# soundpuddle_megawing_mk1.net
KiCad netlist of a schematic drawn in EAGLE
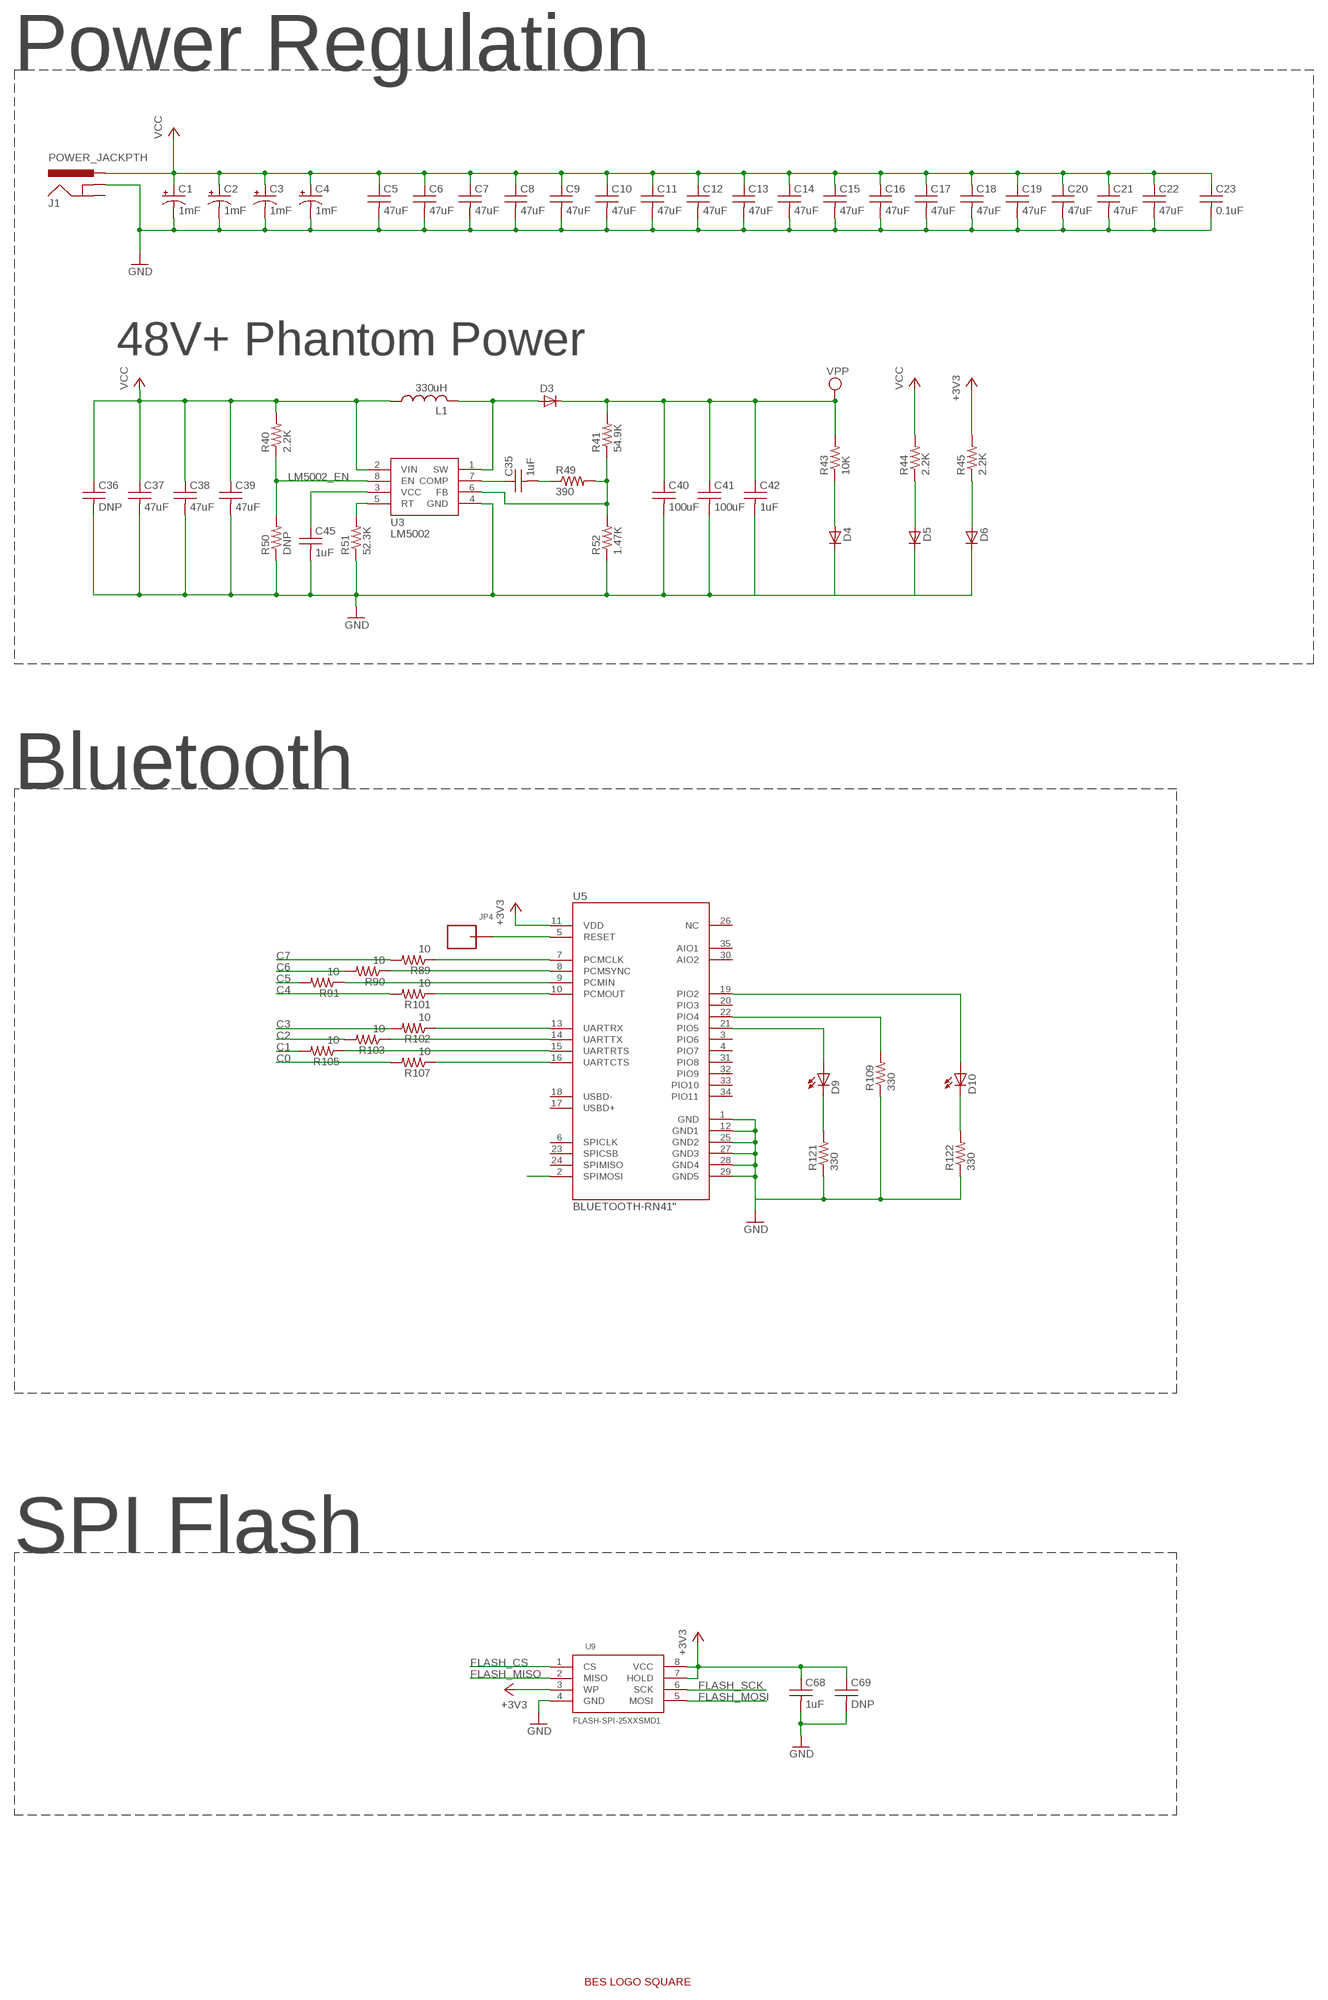
[diagram p0: schematic, sheet 1, part 1 of 3]
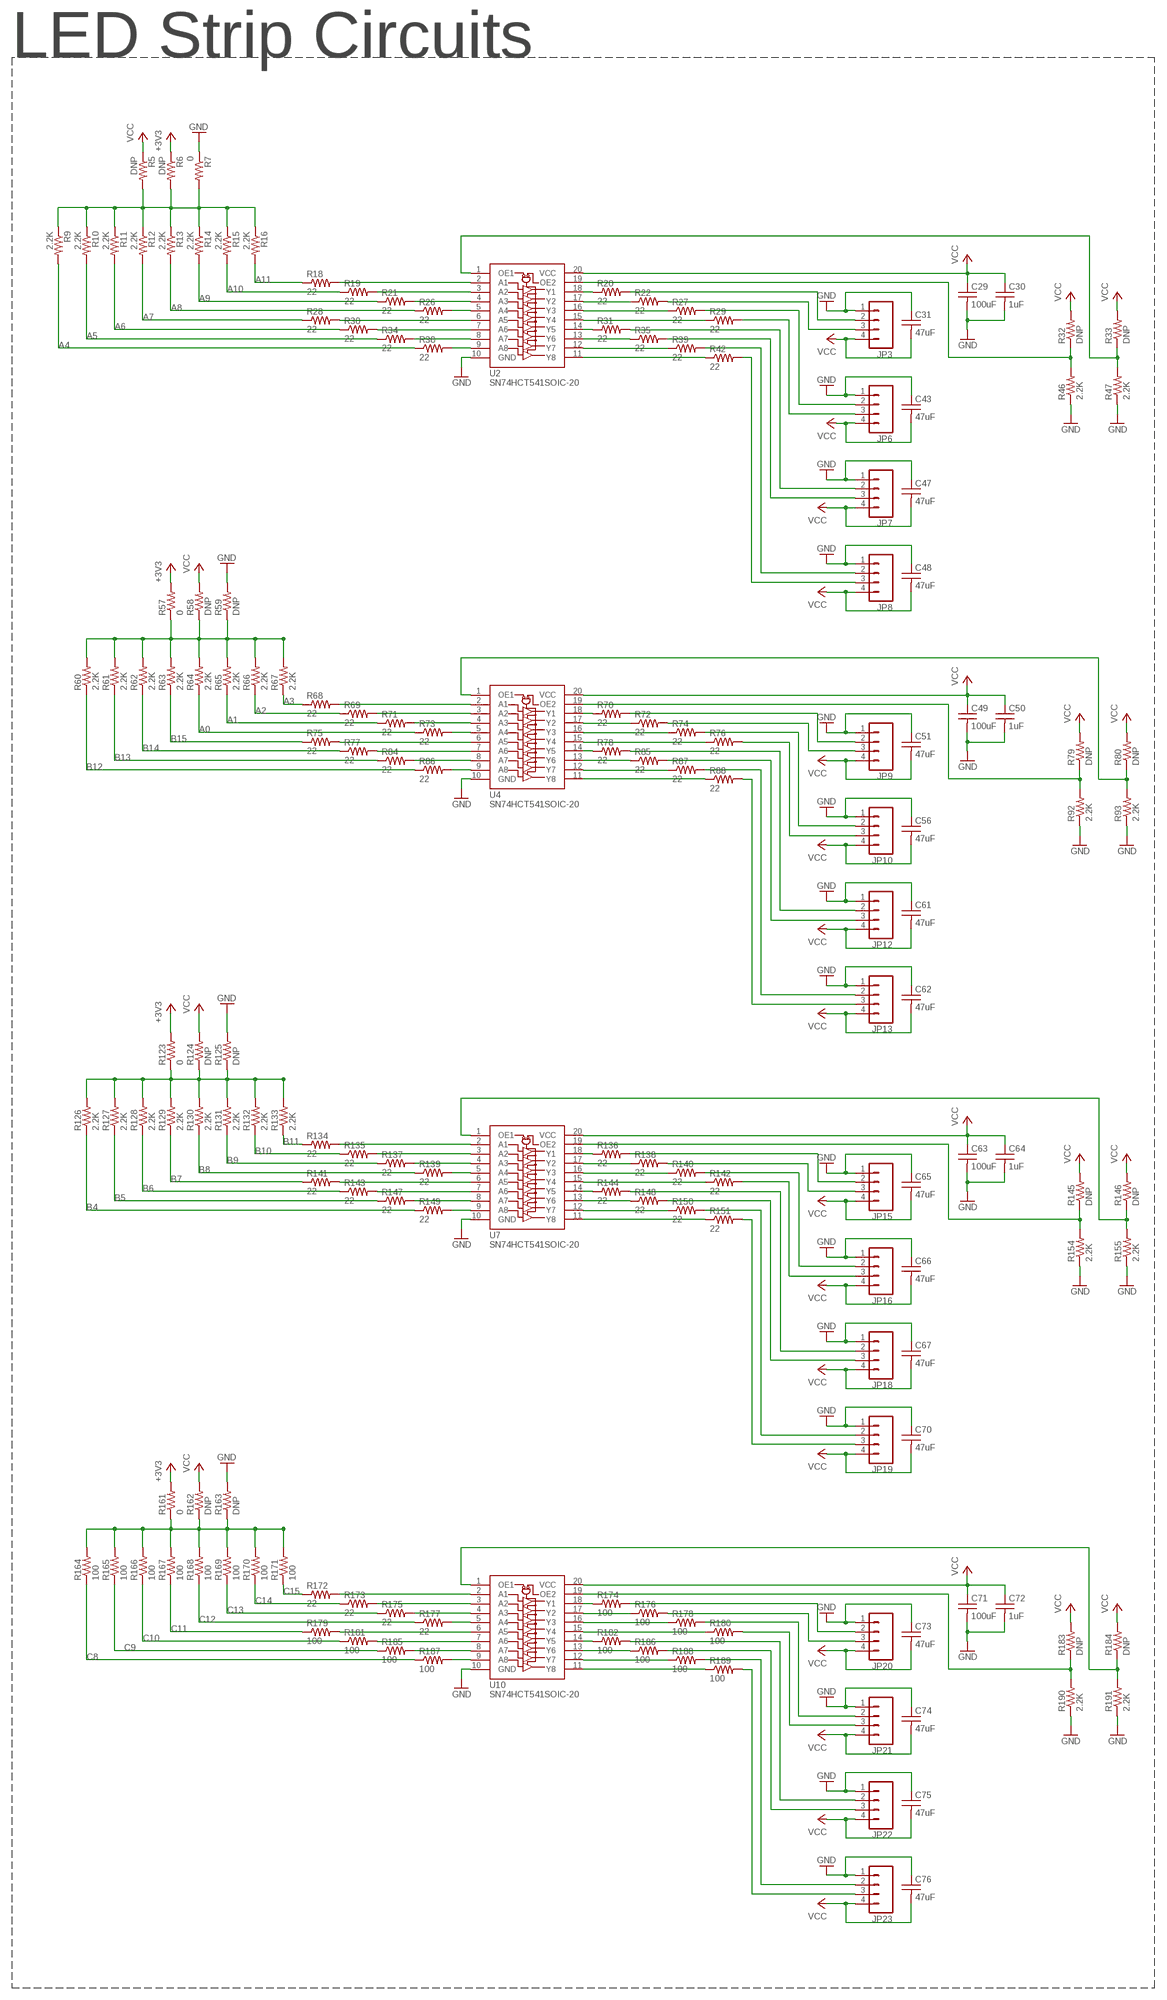
[diagram p1: schematic, sheet 1, part 2 of 3]
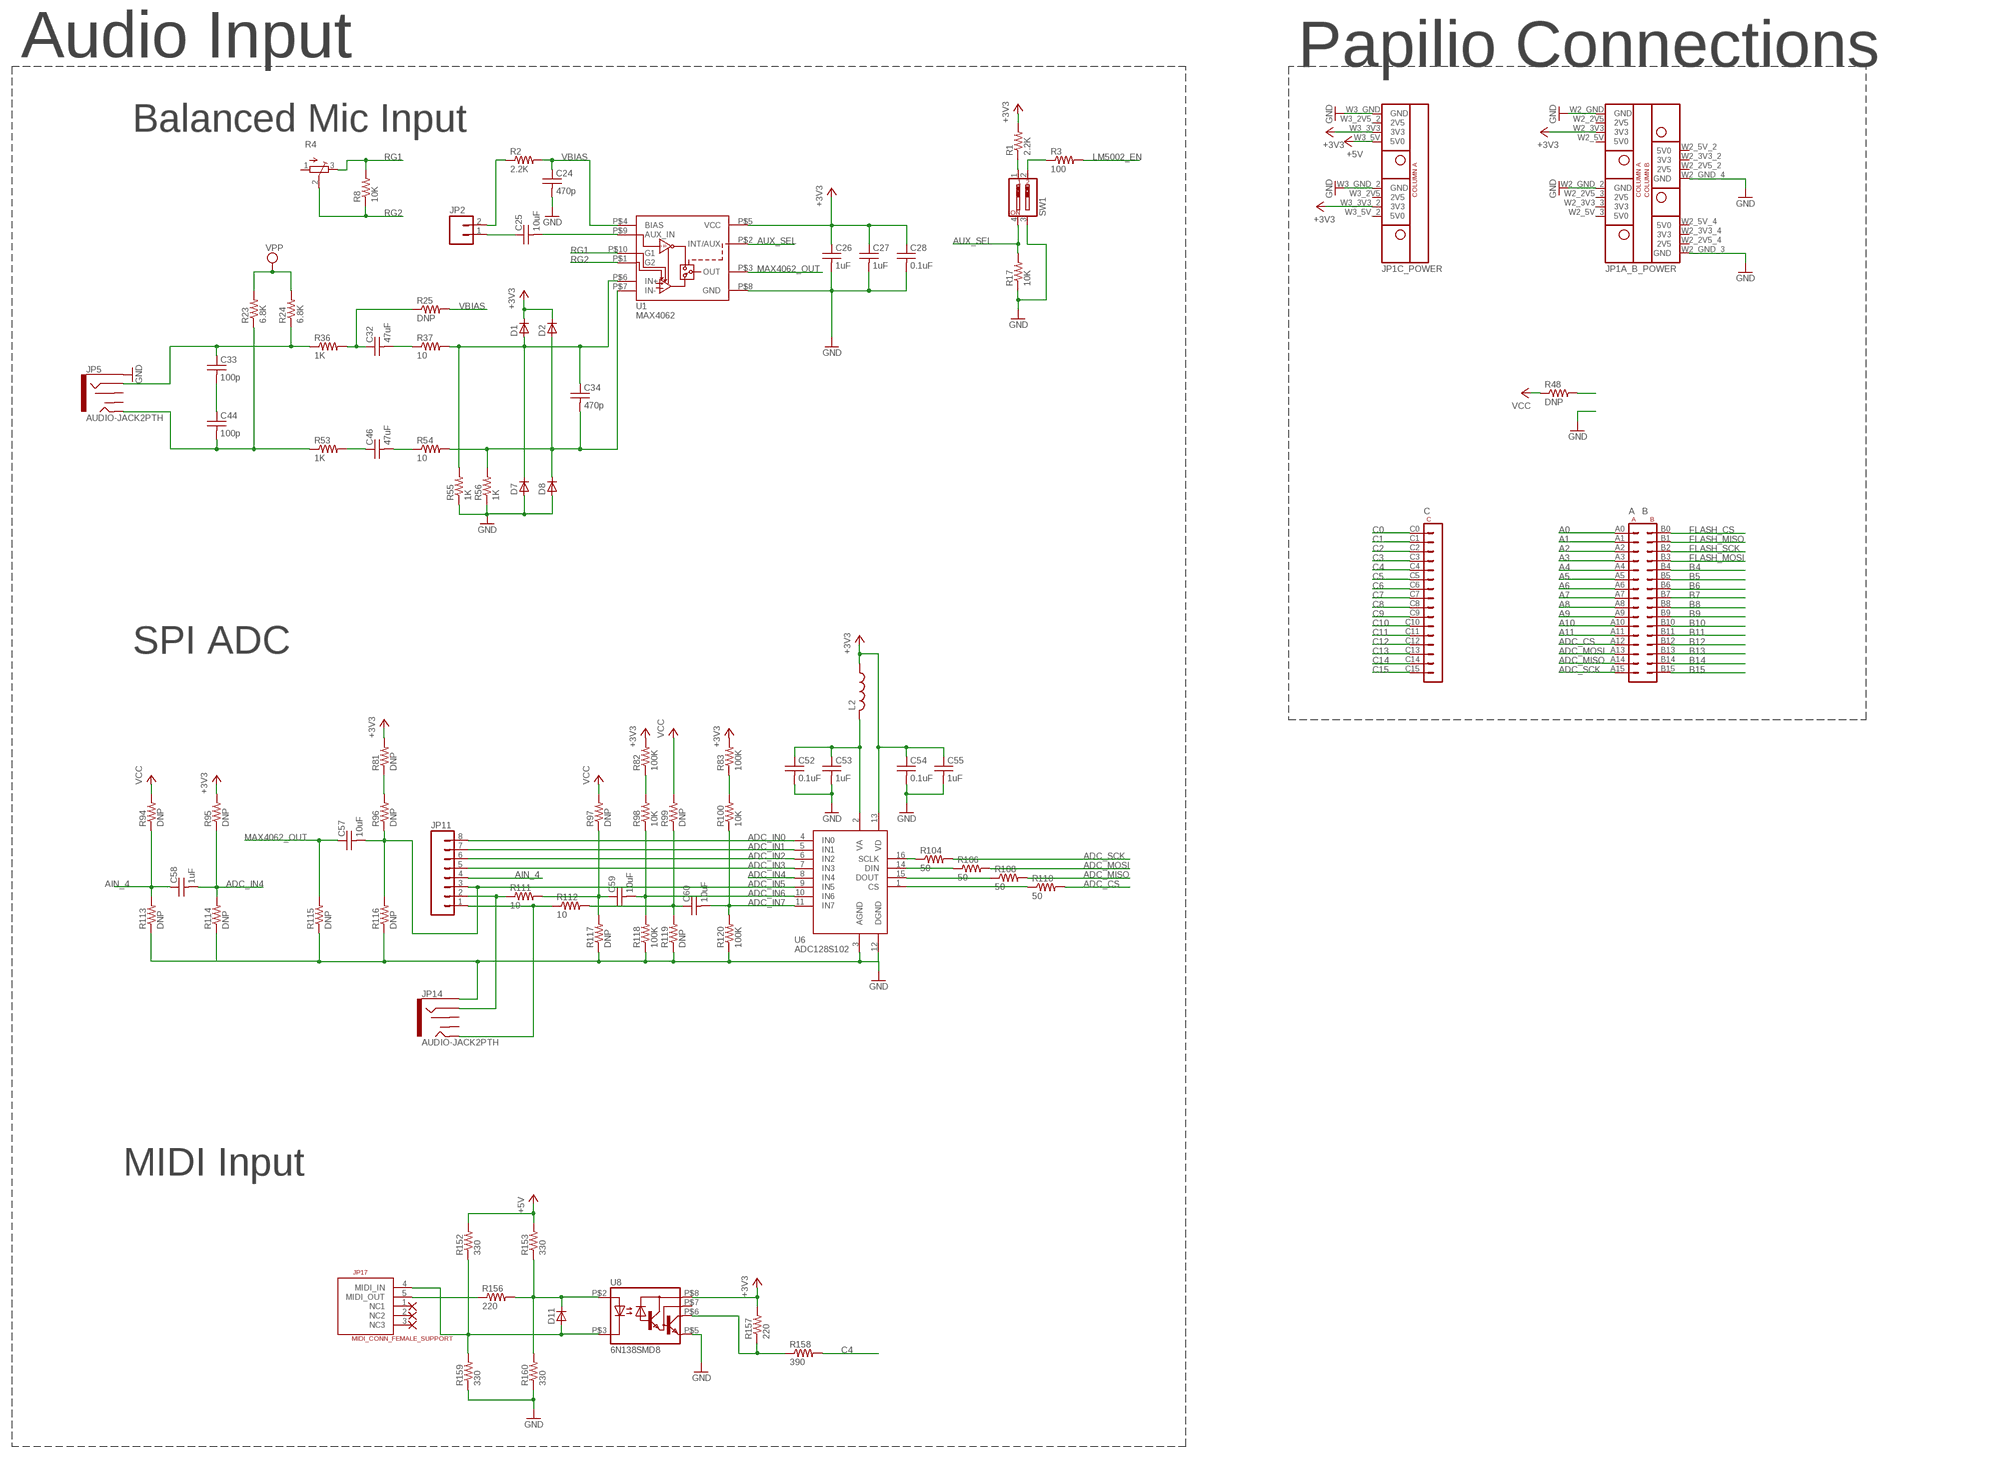
[diagram p2: schematic, sheet 1, part 3 of 3]

(export (version "E")
  (design (tool "Eeschema 10.0.6"))
  (components
    (comp (ref "C1")
      (value "1mF")
      (footprint "eagle-import:E5-8,5")
      (libsource (lib "eagle-import") (part "CPOL-USE5-8.5"))
    )
    (comp (ref "C2")
      (value "1mF")
      (footprint "eagle-import:E5-8,5")
      (libsource (lib "eagle-import") (part "CPOL-USE5-8.5"))
    )
    (comp (ref "C3")
      (value "1mF")
      (footprint "eagle-import:E5-8,5")
      (libsource (lib "eagle-import") (part "CPOL-USE5-8.5"))
    )
    (comp (ref "C4")
      (value "1mF")
      (footprint "eagle-import:E5-8,5")
      (libsource (lib "eagle-import") (part "CPOL-USE5-8.5"))
    )
    (comp (ref "C5")
      (value "47uF")
      (footprint "eagle-import:1206")
      (libsource (lib "eagle-import") (part "CAPACITORC_1206"))
    )
    (comp (ref "C6")
      (value "47uF")
      (footprint "eagle-import:1206")
      (libsource (lib "eagle-import") (part "CAPACITORC_1206"))
    )
    (comp (ref "C7")
      (value "47uF")
      (footprint "eagle-import:1206")
      (libsource (lib "eagle-import") (part "CAPACITORC_1206"))
    )
    (comp (ref "C8")
      (value "47uF")
      (footprint "eagle-import:1206")
      (libsource (lib "eagle-import") (part "CAPACITORC_1206"))
    )
    (comp (ref "C9")
      (value "47uF")
      (footprint "eagle-import:1206")
      (libsource (lib "eagle-import") (part "CAPACITORC_1206"))
    )
    (comp (ref "C10")
      (value "47uF")
      (footprint "eagle-import:1206")
      (libsource (lib "eagle-import") (part "CAPACITORC_1206"))
    )
    (comp (ref "C11")
      (value "47uF")
      (footprint "eagle-import:1206")
      (libsource (lib "eagle-import") (part "CAPACITORC_1206"))
    )
    (comp (ref "C12")
      (value "47uF")
      (footprint "eagle-import:1206")
      (libsource (lib "eagle-import") (part "CAPACITORC_1206"))
    )
    (comp (ref "C13")
      (value "47uF")
      (footprint "eagle-import:1206")
      (libsource (lib "eagle-import") (part "CAPACITORC_1206"))
    )
    (comp (ref "C14")
      (value "47uF")
      (footprint "eagle-import:1206")
      (libsource (lib "eagle-import") (part "CAPACITORC_1206"))
    )
    (comp (ref "C15")
      (value "47uF")
      (footprint "eagle-import:1206")
      (libsource (lib "eagle-import") (part "CAPACITORC_1206"))
    )
    (comp (ref "C16")
      (value "47uF")
      (footprint "eagle-import:1206")
      (libsource (lib "eagle-import") (part "CAPACITORC_1206"))
    )
    (comp (ref "C17")
      (value "47uF")
      (footprint "eagle-import:1206")
      (libsource (lib "eagle-import") (part "CAPACITORC_1206"))
    )
    (comp (ref "C18")
      (value "47uF")
      (footprint "eagle-import:1206")
      (libsource (lib "eagle-import") (part "CAPACITORC_1206"))
    )
    (comp (ref "C19")
      (value "47uF")
      (footprint "eagle-import:1206")
      (libsource (lib "eagle-import") (part "CAPACITORC_1206"))
    )
    (comp (ref "C20")
      (value "47uF")
      (footprint "eagle-import:1206")
      (libsource (lib "eagle-import") (part "CAPACITORC_1206"))
    )
    (comp (ref "C21")
      (value "47uF")
      (footprint "eagle-import:1206")
      (libsource (lib "eagle-import") (part "CAPACITORC_1206"))
    )
    (comp (ref "C22")
      (value "47uF")
      (footprint "eagle-import:1206")
      (libsource (lib "eagle-import") (part "CAPACITORC_1206"))
    )
    (comp (ref "C23")
      (value "0.1uF")
      (footprint "eagle-import:0603")
      (libsource (lib "eagle-import") (part "CAPACITORC_0603"))
    )
    (comp (ref "C24")
      (value "470p")
      (footprint "eagle-import:0603")
      (libsource (lib "eagle-import") (part "CAPACITORC_0603"))
    )
    (comp (ref "C25")
      (value "10uF")
      (footprint "eagle-import:0603")
      (libsource (lib "eagle-import") (part "CAPACITORC_0603"))
    )
    (comp (ref "C26")
      (value "1uF")
      (footprint "eagle-import:0603")
      (libsource (lib "eagle-import") (part "CAPACITORC_0603"))
    )
    (comp (ref "C27")
      (value "1uF")
      (footprint "eagle-import:0603")
      (libsource (lib "eagle-import") (part "CAPACITORC_0603"))
    )
    (comp (ref "C28")
      (value "0.1uF")
      (footprint "eagle-import:0603")
      (libsource (lib "eagle-import") (part "CAPACITORC_0603"))
    )
    (comp (ref "C29")
      (value "100uF")
      (footprint "eagle-import:1206")
      (libsource (lib "eagle-import") (part "CAPACITORC_1206"))
    )
    (comp (ref "C30")
      (value "1uF")
      (footprint "eagle-import:0603")
      (libsource (lib "eagle-import") (part "CAPACITORC_0603"))
    )
    (comp (ref "C31")
      (value "47uF")
      (footprint "eagle-import:1206")
      (libsource (lib "eagle-import") (part "CAPACITORC_1206"))
    )
    (comp (ref "C32")
      (value "47uF")
      (footprint "eagle-import:1206")
      (libsource (lib "eagle-import") (part "CAPACITORC_1206"))
    )
    (comp (ref "C33")
      (value "100p")
      (footprint "eagle-import:0603")
      (libsource (lib "eagle-import") (part "CAPACITORC_0603"))
    )
    (comp (ref "C34")
      (value "470p")
      (footprint "eagle-import:0603")
      (libsource (lib "eagle-import") (part "CAPACITORC_0603"))
    )
    (comp (ref "C35")
      (value "1uF")
      (footprint "eagle-import:0603")
      (libsource (lib "eagle-import") (part "CAPACITORC_0603"))
    )
    (comp (ref "C36")
      (value "DNP")
      (footprint "eagle-import:0603")
      (libsource (lib "eagle-import") (part "CAPACITORC_0603"))
    )
    (comp (ref "C37")
      (value "47uF")
      (footprint "eagle-import:1206")
      (libsource (lib "eagle-import") (part "CAPACITORC_1206"))
    )
    (comp (ref "C38")
      (value "47uF")
      (footprint "eagle-import:1206")
      (libsource (lib "eagle-import") (part "CAPACITORC_1206"))
    )
    (comp (ref "C39")
      (value "47uF")
      (footprint "eagle-import:1206")
      (libsource (lib "eagle-import") (part "CAPACITORC_1206"))
    )
    (comp (ref "C40")
      (value "100uF")
      (footprint "eagle-import:1206")
      (libsource (lib "eagle-import") (part "CAPACITORC_1206"))
    )
    (comp (ref "C41")
      (value "100uF")
      (footprint "eagle-import:1206")
      (libsource (lib "eagle-import") (part "CAPACITORC_1206"))
    )
    (comp (ref "C42")
      (value "1uF")
      (footprint "eagle-import:0603")
      (libsource (lib "eagle-import") (part "CAPACITORC_0603"))
    )
    (comp (ref "C43")
      (value "47uF")
      (footprint "eagle-import:1206")
      (libsource (lib "eagle-import") (part "CAPACITORC_1206"))
    )
    (comp (ref "C44")
      (value "100p")
      (footprint "eagle-import:0603")
      (libsource (lib "eagle-import") (part "CAPACITORC_0603"))
    )
    (comp (ref "C45")
      (value "1uF")
      (footprint "eagle-import:0603")
      (libsource (lib "eagle-import") (part "CAPACITORC_0603"))
    )
    (comp (ref "C46")
      (value "47uF")
      (footprint "eagle-import:1206")
      (libsource (lib "eagle-import") (part "CAPACITORC_1206"))
    )
    (comp (ref "C47")
      (value "47uF")
      (footprint "eagle-import:1206")
      (libsource (lib "eagle-import") (part "CAPACITORC_1206"))
    )
    (comp (ref "C48")
      (value "47uF")
      (footprint "eagle-import:1206")
      (libsource (lib "eagle-import") (part "CAPACITORC_1206"))
    )
    (comp (ref "C49")
      (value "100uF")
      (footprint "eagle-import:1206")
      (libsource (lib "eagle-import") (part "CAPACITORC_1206"))
    )
    (comp (ref "C50")
      (value "1uF")
      (footprint "eagle-import:0603")
      (libsource (lib "eagle-import") (part "CAPACITORC_0603"))
    )
    (comp (ref "C51")
      (value "47uF")
      (footprint "eagle-import:1206")
      (libsource (lib "eagle-import") (part "CAPACITORC_1206"))
    )
    (comp (ref "C52")
      (value "0.1uF")
      (footprint "eagle-import:0603")
      (libsource (lib "eagle-import") (part "CAPACITORC_0603"))
    )
    (comp (ref "C53")
      (value "1uF")
      (footprint "eagle-import:0603")
      (libsource (lib "eagle-import") (part "CAPACITORC_0603"))
    )
    (comp (ref "C54")
      (value "0.1uF")
      (footprint "eagle-import:0603")
      (libsource (lib "eagle-import") (part "CAPACITORC_0603"))
    )
    (comp (ref "C55")
      (value "1uF")
      (footprint "eagle-import:0603")
      (libsource (lib "eagle-import") (part "CAPACITORC_0603"))
    )
    (comp (ref "C56")
      (value "47uF")
      (footprint "eagle-import:1206")
      (libsource (lib "eagle-import") (part "CAPACITORC_1206"))
    )
    (comp (ref "C57")
      (value "10uF")
      (footprint "eagle-import:0603")
      (libsource (lib "eagle-import") (part "CAPACITORC_0603"))
    )
    (comp (ref "C58")
      (value "1uF")
      (footprint "eagle-import:0603")
      (libsource (lib "eagle-import") (part "CAPACITORC_0603"))
    )
    (comp (ref "C59")
      (value "10uF")
      (footprint "eagle-import:0603")
      (libsource (lib "eagle-import") (part "CAPACITORC_0603"))
    )
    (comp (ref "C60")
      (value "10uF")
      (footprint "eagle-import:0603")
      (libsource (lib "eagle-import") (part "CAPACITORC_0603"))
    )
    (comp (ref "C61")
      (value "47uF")
      (footprint "eagle-import:1206")
      (libsource (lib "eagle-import") (part "CAPACITORC_1206"))
    )
    (comp (ref "C62")
      (value "47uF")
      (footprint "eagle-import:1206")
      (libsource (lib "eagle-import") (part "CAPACITORC_1206"))
    )
    (comp (ref "C63")
      (value "100uF")
      (footprint "eagle-import:1206")
      (libsource (lib "eagle-import") (part "CAPACITORC_1206"))
    )
    (comp (ref "C64")
      (value "1uF")
      (footprint "eagle-import:0603")
      (libsource (lib "eagle-import") (part "CAPACITORC_0603"))
    )
    (comp (ref "C65")
      (value "47uF")
      (footprint "eagle-import:1206")
      (libsource (lib "eagle-import") (part "CAPACITORC_1206"))
    )
    (comp (ref "C66")
      (value "47uF")
      (footprint "eagle-import:1206")
      (libsource (lib "eagle-import") (part "CAPACITORC_1206"))
    )
    (comp (ref "C67")
      (value "47uF")
      (footprint "eagle-import:1206")
      (libsource (lib "eagle-import") (part "CAPACITORC_1206"))
    )
    (comp (ref "C68")
      (value "1uF")
      (footprint "eagle-import:0603")
      (libsource (lib "eagle-import") (part "CAPACITORC_0603"))
    )
    (comp (ref "C69")
      (value "DNP")
      (footprint "eagle-import:1206")
      (libsource (lib "eagle-import") (part "CAPACITORC_1206"))
    )
    (comp (ref "C70")
      (value "47uF")
      (footprint "eagle-import:1206")
      (libsource (lib "eagle-import") (part "CAPACITORC_1206"))
    )
    (comp (ref "C71")
      (value "100uF")
      (footprint "eagle-import:1206")
      (libsource (lib "eagle-import") (part "CAPACITORC_1206"))
    )
    (comp (ref "C72")
      (value "1uF")
      (footprint "eagle-import:0603")
      (libsource (lib "eagle-import") (part "CAPACITORC_0603"))
    )
    (comp (ref "C73")
      (value "47uF")
      (footprint "eagle-import:1206")
      (libsource (lib "eagle-import") (part "CAPACITORC_1206"))
    )
    (comp (ref "C74")
      (value "47uF")
      (footprint "eagle-import:1206")
      (libsource (lib "eagle-import") (part "CAPACITORC_1206"))
    )
    (comp (ref "C75")
      (value "47uF")
      (footprint "eagle-import:1206")
      (libsource (lib "eagle-import") (part "CAPACITORC_1206"))
    )
    (comp (ref "C76")
      (value "47uF")
      (footprint "eagle-import:1206")
      (libsource (lib "eagle-import") (part "CAPACITORC_1206"))
    )
    (comp (ref "D1")
      (value "DIODE_SMDSOD-323")
      (footprint "eagle-import:SOD-323")
      (libsource (lib "eagle-import") (part "DIODE_SMDSOD-323"))
    )
    (comp (ref "D2")
      (value "DIODE_SMDSOD-323")
      (footprint "eagle-import:SOD-323")
      (libsource (lib "eagle-import") (part "DIODE_SMDSOD-323"))
    )
    (comp (ref "D3")
      (value "DIODE_SMDSOD-323")
      (footprint "eagle-import:SOD-323")
      (libsource (lib "eagle-import") (part "DIODE_SMDSOD-323"))
    )
    (comp (ref "D4")
      (value "DIODE_SMDSOD-323")
      (footprint "eagle-import:SOD-323")
      (libsource (lib "eagle-import") (part "DIODE_SMDSOD-323"))
    )
    (comp (ref "D5")
      (value "DIODE_SMDSOD-323")
      (footprint "eagle-import:SOD-323")
      (libsource (lib "eagle-import") (part "DIODE_SMDSOD-323"))
    )
    (comp (ref "D6")
      (value "DIODE_SMDSOD-323")
      (footprint "eagle-import:SOD-323")
      (libsource (lib "eagle-import") (part "DIODE_SMDSOD-323"))
    )
    (comp (ref "D7")
      (value "DIODE_SMDSOD-323")
      (footprint "eagle-import:SOD-323")
      (libsource (lib "eagle-import") (part "DIODE_SMDSOD-323"))
    )
    (comp (ref "D8")
      (value "DIODE_SMDSOD-323")
      (footprint "eagle-import:SOD-323")
      (libsource (lib "eagle-import") (part "DIODE_SMDSOD-323"))
    )
    (comp (ref "D9")
      (value "LED0805")
      (footprint "eagle-import:LED_0805")
      (libsource (lib "eagle-import") (part "LED0805"))
    )
    (comp (ref "D10")
      (value "LED0805")
      (footprint "eagle-import:LED_0805")
      (libsource (lib "eagle-import") (part "LED0805"))
    )
    (comp (ref "D11")
      (value "DIODE_SMDSOD-323")
      (footprint "eagle-import:SOD-323")
      (libsource (lib "eagle-import") (part "DIODE_SMDSOD-323"))
    )
    (comp (ref "J1")
      (value "POWER_JACKPTH")
      (footprint "eagle-import:POWER_JACK_PTH")
      (libsource (lib "eagle-import") (part "POWER_JACKPTH"))
    )
    (comp (ref "JP1")
      (value "PAPILIO_PLUS_MEGAWING")
      (footprint "eagle-import:PAPILIO_PLUS")
      (libsource (lib "eagle-import") (part "PAPILIO_PLUS_MEGAWING"))
    )
    (comp (ref "JP2")
      (value "M02PTH")
      (footprint "eagle-import:1X02")
      (libsource (lib "eagle-import") (part "M02PTH"))
    )
    (comp (ref "JP3")
      (value "M04POLAR")
      (footprint "eagle-import:MOLEX-1X4")
      (libsource (lib "eagle-import") (part "M04POLAR"))
    )
    (comp (ref "JP4")
      (value "HEADER-SMALL-1PIN")
      (footprint "eagle-import:HEADER-SMALL-1PIN-0.036IN")
      (libsource (lib "eagle-import") (part "HEADER-SMALL-1PIN"))
    )
    (comp (ref "JP5")
      (value "AUDIO-JACK2PTH")
      (footprint "eagle-import:AUDIO-JACK")
      (libsource (lib "eagle-import") (part "AUDIO-JACK2PTH"))
    )
    (comp (ref "JP6")
      (value "M04POLAR")
      (footprint "eagle-import:MOLEX-1X4")
      (libsource (lib "eagle-import") (part "M04POLAR"))
    )
    (comp (ref "JP7")
      (value "M04POLAR")
      (footprint "eagle-import:MOLEX-1X4")
      (libsource (lib "eagle-import") (part "M04POLAR"))
    )
    (comp (ref "JP8")
      (value "M04POLAR")
      (footprint "eagle-import:MOLEX-1X4")
      (libsource (lib "eagle-import") (part "M04POLAR"))
    )
    (comp (ref "JP9")
      (value "M04POLAR")
      (footprint "eagle-import:MOLEX-1X4")
      (libsource (lib "eagle-import") (part "M04POLAR"))
    )
    (comp (ref "JP10")
      (value "M04POLAR")
      (footprint "eagle-import:MOLEX-1X4")
      (libsource (lib "eagle-import") (part "M04POLAR"))
    )
    (comp (ref "JP11")
      (value "M081X08")
      (footprint "eagle-import:1X08")
      (libsource (lib "eagle-import") (part "M081X08"))
    )
    (comp (ref "JP12")
      (value "M04POLAR")
      (footprint "eagle-import:MOLEX-1X4")
      (libsource (lib "eagle-import") (part "M04POLAR"))
    )
    (comp (ref "JP13")
      (value "M04POLAR")
      (footprint "eagle-import:MOLEX-1X4")
      (libsource (lib "eagle-import") (part "M04POLAR"))
    )
    (comp (ref "JP14")
      (value "AUDIO-JACK2PTH")
      (footprint "eagle-import:AUDIO-JACK")
      (libsource (lib "eagle-import") (part "AUDIO-JACK2PTH"))
    )
    (comp (ref "JP15")
      (value "M04POLAR")
      (footprint "eagle-import:MOLEX-1X4")
      (libsource (lib "eagle-import") (part "M04POLAR"))
    )
    (comp (ref "JP16")
      (value "M04POLAR")
      (footprint "eagle-import:MOLEX-1X4")
      (libsource (lib "eagle-import") (part "M04POLAR"))
    )
    (comp (ref "JP17")
      (value "MIDI_CONN_FEMALE_SUPPORT")
      (footprint "eagle-import:DIN_5_FEMALE_SUPPORT")
      (libsource (lib "eagle-import") (part "MIDI_CONN_FEMALE_SUPPORT"))
    )
    (comp (ref "JP18")
      (value "M04POLAR")
      (footprint "eagle-import:MOLEX-1X4")
      (libsource (lib "eagle-import") (part "M04POLAR"))
    )
    (comp (ref "JP19")
      (value "M04POLAR")
      (footprint "eagle-import:MOLEX-1X4")
      (libsource (lib "eagle-import") (part "M04POLAR"))
    )
    (comp (ref "JP20")
      (value "M04POLAR")
      (footprint "eagle-import:MOLEX-1X4")
      (libsource (lib "eagle-import") (part "M04POLAR"))
    )
    (comp (ref "JP21")
      (value "M04POLAR")
      (footprint "eagle-import:MOLEX-1X4")
      (libsource (lib "eagle-import") (part "M04POLAR"))
    )
    (comp (ref "JP22")
      (value "M04POLAR")
      (footprint "eagle-import:MOLEX-1X4")
      (libsource (lib "eagle-import") (part "M04POLAR"))
    )
    (comp (ref "JP23")
      (value "M04POLAR")
      (footprint "eagle-import:MOLEX-1X4")
      (libsource (lib "eagle-import") (part "M04POLAR"))
    )
    (comp (ref "L1")
      (value "330uH")
      (footprint "eagle-import:INDUCTOR_10X10MM")
      (libsource (lib "eagle-import") (part "INDUCTOR10X10MM"))
    )
    (comp (ref "L2")
      (value "INDUCTOR0603")
      (footprint "eagle-import:0603")
      (libsource (lib "eagle-import") (part "INDUCTOR0603"))
    )
    (comp (ref "LOGO1")
      (value "LOGO")
      (footprint "eagle-import:LOGO")
      (libsource (lib "eagle-import") (part "LOGO"))
    )
    (comp (ref "R1")
      (value "2.2K")
      (footprint "eagle-import:0603")
      (libsource (lib "eagle-import") (part "RESISTORR_0603"))
    )
    (comp (ref "R2")
      (value "2.2K")
      (footprint "eagle-import:0603")
      (libsource (lib "eagle-import") (part "RESISTORR_0603"))
    )
    (comp (ref "R3")
      (value "100")
      (footprint "eagle-import:0603")
      (libsource (lib "eagle-import") (part "RESISTORR_0603"))
    )
    (comp (ref "R4")
      (value "TRIMPOTTC33X")
      (footprint "eagle-import:TC33X")
      (libsource (lib "eagle-import") (part "TRIMPOTTC33X"))
    )
    (comp (ref "R5")
      (value "DNP")
      (footprint "eagle-import:0603")
      (libsource (lib "eagle-import") (part "RESISTORR_0603"))
    )
    (comp (ref "R6")
      (value "DNP")
      (footprint "eagle-import:0603")
      (libsource (lib "eagle-import") (part "RESISTORR_0603"))
    )
    (comp (ref "R7")
      (value "0")
      (footprint "eagle-import:0603")
      (libsource (lib "eagle-import") (part "RESISTORR_0603"))
    )
    (comp (ref "R8")
      (value "10K")
      (footprint "eagle-import:0603")
      (libsource (lib "eagle-import") (part "RESISTORR_0603"))
    )
    (comp (ref "R9")
      (value "2.2K")
      (footprint "eagle-import:0603")
      (libsource (lib "eagle-import") (part "RESISTORR_0603"))
    )
    (comp (ref "R10")
      (value "2.2K")
      (footprint "eagle-import:0603")
      (libsource (lib "eagle-import") (part "RESISTORR_0603"))
    )
    (comp (ref "R11")
      (value "2.2K")
      (footprint "eagle-import:0603")
      (libsource (lib "eagle-import") (part "RESISTORR_0603"))
    )
    (comp (ref "R12")
      (value "2.2K")
      (footprint "eagle-import:0603")
      (libsource (lib "eagle-import") (part "RESISTORR_0603"))
    )
    (comp (ref "R13")
      (value "2.2K")
      (footprint "eagle-import:0603")
      (libsource (lib "eagle-import") (part "RESISTORR_0603"))
    )
    (comp (ref "R14")
      (value "2.2K")
      (footprint "eagle-import:0603")
      (libsource (lib "eagle-import") (part "RESISTORR_0603"))
    )
    (comp (ref "R15")
      (value "2.2K")
      (footprint "eagle-import:0603")
      (libsource (lib "eagle-import") (part "RESISTORR_0603"))
    )
    (comp (ref "R16")
      (value "2.2K")
      (footprint "eagle-import:0603")
      (libsource (lib "eagle-import") (part "RESISTORR_0603"))
    )
    (comp (ref "R17")
      (value "10K")
      (footprint "eagle-import:0603")
      (libsource (lib "eagle-import") (part "RESISTORR_0603"))
    )
    (comp (ref "R18")
      (value "22")
      (footprint "eagle-import:0603")
      (libsource (lib "eagle-import") (part "RESISTORR_0603"))
    )
    (comp (ref "R19")
      (value "22")
      (footprint "eagle-import:0603")
      (libsource (lib "eagle-import") (part "RESISTORR_0603"))
    )
    (comp (ref "R20")
      (value "22")
      (footprint "eagle-import:0603")
      (libsource (lib "eagle-import") (part "RESISTORR_0603"))
    )
    (comp (ref "R21")
      (value "22")
      (footprint "eagle-import:0603")
      (libsource (lib "eagle-import") (part "RESISTORR_0603"))
    )
    (comp (ref "R22")
      (value "22")
      (footprint "eagle-import:0603")
      (libsource (lib "eagle-import") (part "RESISTORR_0603"))
    )
    (comp (ref "R23")
      (value "6.8K")
      (footprint "eagle-import:0603")
      (libsource (lib "eagle-import") (part "RESISTORR_0603"))
    )
    (comp (ref "R24")
      (value "6.8K")
      (footprint "eagle-import:0603")
      (libsource (lib "eagle-import") (part "RESISTORR_0603"))
    )
    (comp (ref "R25")
      (value "DNP")
      (footprint "eagle-import:0603")
      (libsource (lib "eagle-import") (part "RESISTORR_0603"))
    )
    (comp (ref "R26")
      (value "22")
      (footprint "eagle-import:0603")
      (libsource (lib "eagle-import") (part "RESISTORR_0603"))
    )
    (comp (ref "R27")
      (value "22")
      (footprint "eagle-import:0603")
      (libsource (lib "eagle-import") (part "RESISTORR_0603"))
    )
    (comp (ref "R28")
      (value "22")
      (footprint "eagle-import:0603")
      (libsource (lib "eagle-import") (part "RESISTORR_0603"))
    )
    (comp (ref "R29")
      (value "22")
      (footprint "eagle-import:0603")
      (libsource (lib "eagle-import") (part "RESISTORR_0603"))
    )
    (comp (ref "R30")
      (value "22")
      (footprint "eagle-import:0603")
      (libsource (lib "eagle-import") (part "RESISTORR_0603"))
    )
    (comp (ref "R31")
      (value "22")
      (footprint "eagle-import:0603")
      (libsource (lib "eagle-import") (part "RESISTORR_0603"))
    )
    (comp (ref "R32")
      (value "DNP")
      (footprint "eagle-import:0603")
      (libsource (lib "eagle-import") (part "RESISTORR_0603"))
    )
    (comp (ref "R33")
      (value "DNP")
      (footprint "eagle-import:0603")
      (libsource (lib "eagle-import") (part "RESISTORR_0603"))
    )
    (comp (ref "R34")
      (value "22")
      (footprint "eagle-import:0603")
      (libsource (lib "eagle-import") (part "RESISTORR_0603"))
    )
    (comp (ref "R35")
      (value "22")
      (footprint "eagle-import:0603")
      (libsource (lib "eagle-import") (part "RESISTORR_0603"))
    )
    (comp (ref "R36")
      (value "1K")
      (footprint "eagle-import:0603")
      (libsource (lib "eagle-import") (part "RESISTORR_0603"))
    )
    (comp (ref "R37")
      (value "10")
      (footprint "eagle-import:0603")
      (libsource (lib "eagle-import") (part "RESISTORR_0603"))
    )
    (comp (ref "R38")
      (value "22")
      (footprint "eagle-import:0603")
      (libsource (lib "eagle-import") (part "RESISTORR_0603"))
    )
    (comp (ref "R39")
      (value "22")
      (footprint "eagle-import:0603")
      (libsource (lib "eagle-import") (part "RESISTORR_0603"))
    )
    (comp (ref "R40")
      (value "2.2K")
      (footprint "eagle-import:0603")
      (libsource (lib "eagle-import") (part "RESISTORR_0603"))
    )
    (comp (ref "R41")
      (value "54.9K")
      (footprint "eagle-import:0603")
      (libsource (lib "eagle-import") (part "RESISTORR_0603"))
    )
    (comp (ref "R42")
      (value "22")
      (footprint "eagle-import:0603")
      (libsource (lib "eagle-import") (part "RESISTORR_0603"))
    )
    (comp (ref "R43")
      (value "10K")
      (footprint "eagle-import:0603")
      (libsource (lib "eagle-import") (part "RESISTORR_0603"))
    )
    (comp (ref "R44")
      (value "2.2K")
      (footprint "eagle-import:0603")
      (libsource (lib "eagle-import") (part "RESISTORR_0603"))
    )
    (comp (ref "R45")
      (value "2.2K")
      (footprint "eagle-import:0603")
      (libsource (lib "eagle-import") (part "RESISTORR_0603"))
    )
    (comp (ref "R46")
      (value "2.2K")
      (footprint "eagle-import:0603")
      (libsource (lib "eagle-import") (part "RESISTORR_0603"))
    )
    (comp (ref "R47")
      (value "2.2K")
      (footprint "eagle-import:0603")
      (libsource (lib "eagle-import") (part "RESISTORR_0603"))
    )
    (comp (ref "R48")
      (value "DNP")
      (footprint "eagle-import:0603")
      (libsource (lib "eagle-import") (part "RESISTORR_0603"))
    )
    (comp (ref "R49")
      (value "390")
      (footprint "eagle-import:0603")
      (libsource (lib "eagle-import") (part "RESISTORR_0603"))
    )
    (comp (ref "R50")
      (value "DNP")
      (footprint "eagle-import:0603")
      (libsource (lib "eagle-import") (part "RESISTORR_0603"))
    )
    (comp (ref "R51")
      (value "52.3K")
      (footprint "eagle-import:0603")
      (libsource (lib "eagle-import") (part "RESISTORR_0603"))
    )
    (comp (ref "R52")
      (value "1.47K")
      (footprint "eagle-import:0603")
      (libsource (lib "eagle-import") (part "RESISTORR_0603"))
    )
    (comp (ref "R53")
      (value "1K")
      (footprint "eagle-import:0603")
      (libsource (lib "eagle-import") (part "RESISTORR_0603"))
    )
    (comp (ref "R54")
      (value "10")
      (footprint "eagle-import:0603")
      (libsource (lib "eagle-import") (part "RESISTORR_0603"))
    )
    (comp (ref "R55")
      (value "1K")
      (footprint "eagle-import:0603")
      (libsource (lib "eagle-import") (part "RESISTORR_0603"))
    )
    (comp (ref "R56")
      (value "1K")
      (footprint "eagle-import:0603")
      (libsource (lib "eagle-import") (part "RESISTORR_0603"))
    )
    (comp (ref "R57")
      (value "0")
      (footprint "eagle-import:0603")
      (libsource (lib "eagle-import") (part "RESISTORR_0603"))
    )
    (comp (ref "R58")
      (value "DNP")
      (footprint "eagle-import:0603")
      (libsource (lib "eagle-import") (part "RESISTORR_0603"))
    )
    (comp (ref "R59")
      (value "DNP")
      (footprint "eagle-import:0603")
      (libsource (lib "eagle-import") (part "RESISTORR_0603"))
    )
    (comp (ref "R60")
      (value "2.2K")
      (footprint "eagle-import:0603")
      (libsource (lib "eagle-import") (part "RESISTORR_0603"))
    )
    (comp (ref "R61")
      (value "2.2K")
      (footprint "eagle-import:0603")
      (libsource (lib "eagle-import") (part "RESISTORR_0603"))
    )
    (comp (ref "R62")
      (value "2.2K")
      (footprint "eagle-import:0603")
      (libsource (lib "eagle-import") (part "RESISTORR_0603"))
    )
    (comp (ref "R63")
      (value "2.2K")
      (footprint "eagle-import:0603")
      (libsource (lib "eagle-import") (part "RESISTORR_0603"))
    )
    (comp (ref "R64")
      (value "2.2K")
      (footprint "eagle-import:0603")
      (libsource (lib "eagle-import") (part "RESISTORR_0603"))
    )
    (comp (ref "R65")
      (value "2.2K")
      (footprint "eagle-import:0603")
      (libsource (lib "eagle-import") (part "RESISTORR_0603"))
    )
    (comp (ref "R66")
      (value "2.2K")
      (footprint "eagle-import:0603")
      (libsource (lib "eagle-import") (part "RESISTORR_0603"))
    )
    (comp (ref "R67")
      (value "2.2K")
      (footprint "eagle-import:0603")
      (libsource (lib "eagle-import") (part "RESISTORR_0603"))
    )
    (comp (ref "R68")
      (value "22")
      (footprint "eagle-import:0603")
      (libsource (lib "eagle-import") (part "RESISTORR_0603"))
    )
    (comp (ref "R69")
      (value "22")
      (footprint "eagle-import:0603")
      (libsource (lib "eagle-import") (part "RESISTORR_0603"))
    )
    (comp (ref "R70")
      (value "22")
      (footprint "eagle-import:0603")
      (libsource (lib "eagle-import") (part "RESISTORR_0603"))
    )
    (comp (ref "R71")
      (value "22")
      (footprint "eagle-import:0603")
      (libsource (lib "eagle-import") (part "RESISTORR_0603"))
    )
    (comp (ref "R72")
      (value "22")
      (footprint "eagle-import:0603")
      (libsource (lib "eagle-import") (part "RESISTORR_0603"))
    )
    (comp (ref "R73")
      (value "22")
      (footprint "eagle-import:0603")
      (libsource (lib "eagle-import") (part "RESISTORR_0603"))
    )
    (comp (ref "R74")
      (value "22")
      (footprint "eagle-import:0603")
      (libsource (lib "eagle-import") (part "RESISTORR_0603"))
    )
    (comp (ref "R75")
      (value "22")
      (footprint "eagle-import:0603")
      (libsource (lib "eagle-import") (part "RESISTORR_0603"))
    )
    (comp (ref "R76")
      (value "22")
      (footprint "eagle-import:0603")
      (libsource (lib "eagle-import") (part "RESISTORR_0603"))
    )
    (comp (ref "R77")
      (value "22")
      (footprint "eagle-import:0603")
      (libsource (lib "eagle-import") (part "RESISTORR_0603"))
    )
    (comp (ref "R78")
      (value "22")
      (footprint "eagle-import:0603")
      (libsource (lib "eagle-import") (part "RESISTORR_0603"))
    )
    (comp (ref "R79")
      (value "DNP")
      (footprint "eagle-import:0603")
      (libsource (lib "eagle-import") (part "RESISTORR_0603"))
    )
    (comp (ref "R80")
      (value "DNP")
      (footprint "eagle-import:0603")
      (libsource (lib "eagle-import") (part "RESISTORR_0603"))
    )
    (comp (ref "R81")
      (value "DNP")
      (footprint "eagle-import:0603")
      (libsource (lib "eagle-import") (part "RESISTORR_0603"))
    )
    (comp (ref "R82")
      (value "100K")
      (footprint "eagle-import:0603")
      (libsource (lib "eagle-import") (part "RESISTORR_0603"))
    )
    (comp (ref "R83")
      (value "100K")
      (footprint "eagle-import:0603")
      (libsource (lib "eagle-import") (part "RESISTORR_0603"))
    )
    (comp (ref "R84")
      (value "22")
      (footprint "eagle-import:0603")
      (libsource (lib "eagle-import") (part "RESISTORR_0603"))
    )
    (comp (ref "R85")
      (value "22")
      (footprint "eagle-import:0603")
      (libsource (lib "eagle-import") (part "RESISTORR_0603"))
    )
    (comp (ref "R86")
      (value "22")
      (footprint "eagle-import:0603")
      (libsource (lib "eagle-import") (part "RESISTORR_0603"))
    )
    (comp (ref "R87")
      (value "22")
      (footprint "eagle-import:0603")
      (libsource (lib "eagle-import") (part "RESISTORR_0603"))
    )
    (comp (ref "R88")
      (value "22")
      (footprint "eagle-import:0603")
      (libsource (lib "eagle-import") (part "RESISTORR_0603"))
    )
    (comp (ref "R89")
      (value "10")
      (footprint "eagle-import:0603")
      (libsource (lib "eagle-import") (part "RESISTORR_0603"))
    )
    (comp (ref "R90")
      (value "10")
      (footprint "eagle-import:0603")
      (libsource (lib "eagle-import") (part "RESISTORR_0603"))
    )
    (comp (ref "R91")
      (value "10")
      (footprint "eagle-import:0603")
      (libsource (lib "eagle-import") (part "RESISTORR_0603"))
    )
    (comp (ref "R92")
      (value "2.2K")
      (footprint "eagle-import:0603")
      (libsource (lib "eagle-import") (part "RESISTORR_0603"))
    )
    (comp (ref "R93")
      (value "2.2K")
      (footprint "eagle-import:0603")
      (libsource (lib "eagle-import") (part "RESISTORR_0603"))
    )
    (comp (ref "R94")
      (value "DNP")
      (footprint "eagle-import:0603")
      (libsource (lib "eagle-import") (part "RESISTORR_0603"))
    )
    (comp (ref "R95")
      (value "DNP")
      (footprint "eagle-import:0603")
      (libsource (lib "eagle-import") (part "RESISTORR_0603"))
    )
    (comp (ref "R96")
      (value "DNP")
      (footprint "eagle-import:0603")
      (libsource (lib "eagle-import") (part "RESISTORR_0603"))
    )
    (comp (ref "R97")
      (value "DNP")
      (footprint "eagle-import:0603")
      (libsource (lib "eagle-import") (part "RESISTORR_0603"))
    )
    (comp (ref "R98")
      (value "10K")
      (footprint "eagle-import:0603")
      (libsource (lib "eagle-import") (part "RESISTORR_0603"))
    )
    (comp (ref "R99")
      (value "DNP")
      (footprint "eagle-import:0603")
      (libsource (lib "eagle-import") (part "RESISTORR_0603"))
    )
    (comp (ref "R100")
      (value "10K")
      (footprint "eagle-import:0603")
      (libsource (lib "eagle-import") (part "RESISTORR_0603"))
    )
    (comp (ref "R101")
      (value "10")
      (footprint "eagle-import:0603")
      (libsource (lib "eagle-import") (part "RESISTORR_0603"))
    )
    (comp (ref "R102")
      (value "10")
      (footprint "eagle-import:0603")
      (libsource (lib "eagle-import") (part "RESISTORR_0603"))
    )
    (comp (ref "R103")
      (value "10")
      (footprint "eagle-import:0603")
      (libsource (lib "eagle-import") (part "RESISTORR_0603"))
    )
    (comp (ref "R104")
      (value "50")
      (footprint "eagle-import:0603")
      (libsource (lib "eagle-import") (part "RESISTORR_0603"))
    )
    (comp (ref "R105")
      (value "10")
      (footprint "eagle-import:0603")
      (libsource (lib "eagle-import") (part "RESISTORR_0603"))
    )
    (comp (ref "R106")
      (value "50")
      (footprint "eagle-import:0603")
      (libsource (lib "eagle-import") (part "RESISTORR_0603"))
    )
    (comp (ref "R107")
      (value "10")
      (footprint "eagle-import:0603")
      (libsource (lib "eagle-import") (part "RESISTORR_0603"))
    )
    (comp (ref "R108")
      (value "50")
      (footprint "eagle-import:0603")
      (libsource (lib "eagle-import") (part "RESISTORR_0603"))
    )
    (comp (ref "R109")
      (value "330")
      (footprint "eagle-import:0603")
      (libsource (lib "eagle-import") (part "RESISTORR_0603"))
    )
    (comp (ref "R110")
      (value "50")
      (footprint "eagle-import:0603")
      (libsource (lib "eagle-import") (part "RESISTORR_0603"))
    )
    (comp (ref "R111")
      (value "10")
      (footprint "eagle-import:0603")
      (libsource (lib "eagle-import") (part "RESISTORR_0603"))
    )
    (comp (ref "R112")
      (value "10")
      (footprint "eagle-import:0603")
      (libsource (lib "eagle-import") (part "RESISTORR_0603"))
    )
    (comp (ref "R113")
      (value "DNP")
      (footprint "eagle-import:0603")
      (libsource (lib "eagle-import") (part "RESISTORR_0603"))
    )
    (comp (ref "R114")
      (value "DNP")
      (footprint "eagle-import:0603")
      (libsource (lib "eagle-import") (part "RESISTORR_0603"))
    )
    (comp (ref "R115")
      (value "DNP")
      (footprint "eagle-import:0603")
      (libsource (lib "eagle-import") (part "RESISTORR_0603"))
    )
    (comp (ref "R116")
      (value "DNP")
      (footprint "eagle-import:0603")
      (libsource (lib "eagle-import") (part "RESISTORR_0603"))
    )
    (comp (ref "R117")
      (value "DNP")
      (footprint "eagle-import:0603")
      (libsource (lib "eagle-import") (part "RESISTORR_0603"))
    )
    (comp (ref "R118")
      (value "100K")
      (footprint "eagle-import:0603")
      (libsource (lib "eagle-import") (part "RESISTORR_0603"))
    )
    (comp (ref "R119")
      (value "DNP")
      (footprint "eagle-import:0603")
      (libsource (lib "eagle-import") (part "RESISTORR_0603"))
    )
    (comp (ref "R120")
      (value "100K")
      (footprint "eagle-import:0603")
      (libsource (lib "eagle-import") (part "RESISTORR_0603"))
    )
    (comp (ref "R121")
      (value "330")
      (footprint "eagle-import:0603")
      (libsource (lib "eagle-import") (part "RESISTORR_0603"))
    )
    (comp (ref "R122")
      (value "330")
      (footprint "eagle-import:0603")
      (libsource (lib "eagle-import") (part "RESISTORR_0603"))
    )
    (comp (ref "R123")
      (value "0")
      (footprint "eagle-import:0603")
      (libsource (lib "eagle-import") (part "RESISTORR_0603"))
    )
    (comp (ref "R124")
      (value "DNP")
      (footprint "eagle-import:0603")
      (libsource (lib "eagle-import") (part "RESISTORR_0603"))
    )
    (comp (ref "R125")
      (value "DNP")
      (footprint "eagle-import:0603")
      (libsource (lib "eagle-import") (part "RESISTORR_0603"))
    )
    (comp (ref "R126")
      (value "2.2K")
      (footprint "eagle-import:0603")
      (libsource (lib "eagle-import") (part "RESISTORR_0603"))
    )
    (comp (ref "R127")
      (value "2.2K")
      (footprint "eagle-import:0603")
      (libsource (lib "eagle-import") (part "RESISTORR_0603"))
    )
    (comp (ref "R128")
      (value "2.2K")
      (footprint "eagle-import:0603")
      (libsource (lib "eagle-import") (part "RESISTORR_0603"))
    )
    (comp (ref "R129")
      (value "2.2K")
      (footprint "eagle-import:0603")
      (libsource (lib "eagle-import") (part "RESISTORR_0603"))
    )
    (comp (ref "R130")
      (value "2.2K")
      (footprint "eagle-import:0603")
      (libsource (lib "eagle-import") (part "RESISTORR_0603"))
    )
    (comp (ref "R131")
      (value "2.2K")
      (footprint "eagle-import:0603")
      (libsource (lib "eagle-import") (part "RESISTORR_0603"))
    )
    (comp (ref "R132")
      (value "2.2K")
      (footprint "eagle-import:0603")
      (libsource (lib "eagle-import") (part "RESISTORR_0603"))
    )
    (comp (ref "R133")
      (value "2.2K")
      (footprint "eagle-import:0603")
      (libsource (lib "eagle-import") (part "RESISTORR_0603"))
    )
    (comp (ref "R134")
      (value "22")
      (footprint "eagle-import:0603")
      (libsource (lib "eagle-import") (part "RESISTORR_0603"))
    )
    (comp (ref "R135")
      (value "22")
      (footprint "eagle-import:0603")
      (libsource (lib "eagle-import") (part "RESISTORR_0603"))
    )
    (comp (ref "R136")
      (value "22")
      (footprint "eagle-import:0603")
      (libsource (lib "eagle-import") (part "RESISTORR_0603"))
    )
    (comp (ref "R137")
      (value "22")
      (footprint "eagle-import:0603")
      (libsource (lib "eagle-import") (part "RESISTORR_0603"))
    )
    (comp (ref "R138")
      (value "22")
      (footprint "eagle-import:0603")
      (libsource (lib "eagle-import") (part "RESISTORR_0603"))
    )
    (comp (ref "R139")
      (value "22")
      (footprint "eagle-import:0603")
      (libsource (lib "eagle-import") (part "RESISTORR_0603"))
    )
    (comp (ref "R140")
      (value "22")
      (footprint "eagle-import:0603")
      (libsource (lib "eagle-import") (part "RESISTORR_0603"))
    )
    (comp (ref "R141")
      (value "22")
      (footprint "eagle-import:0603")
      (libsource (lib "eagle-import") (part "RESISTORR_0603"))
    )
    (comp (ref "R142")
      (value "22")
      (footprint "eagle-import:0603")
      (libsource (lib "eagle-import") (part "RESISTORR_0603"))
    )
    (comp (ref "R143")
      (value "22")
      (footprint "eagle-import:0603")
      (libsource (lib "eagle-import") (part "RESISTORR_0603"))
    )
    (comp (ref "R144")
      (value "22")
      (footprint "eagle-import:0603")
      (libsource (lib "eagle-import") (part "RESISTORR_0603"))
    )
    (comp (ref "R145")
      (value "DNP")
      (footprint "eagle-import:0603")
      (libsource (lib "eagle-import") (part "RESISTORR_0603"))
    )
    (comp (ref "R146")
      (value "DNP")
      (footprint "eagle-import:0603")
      (libsource (lib "eagle-import") (part "RESISTORR_0603"))
    )
    (comp (ref "R147")
      (value "22")
      (footprint "eagle-import:0603")
      (libsource (lib "eagle-import") (part "RESISTORR_0603"))
    )
    (comp (ref "R148")
      (value "22")
      (footprint "eagle-import:0603")
      (libsource (lib "eagle-import") (part "RESISTORR_0603"))
    )
    (comp (ref "R149")
      (value "22")
      (footprint "eagle-import:0603")
      (libsource (lib "eagle-import") (part "RESISTORR_0603"))
    )
    (comp (ref "R150")
      (value "22")
      (footprint "eagle-import:0603")
      (libsource (lib "eagle-import") (part "RESISTORR_0603"))
    )
    (comp (ref "R151")
      (value "22")
      (footprint "eagle-import:0603")
      (libsource (lib "eagle-import") (part "RESISTORR_0603"))
    )
    (comp (ref "R152")
      (value "330")
      (footprint "eagle-import:0603")
      (libsource (lib "eagle-import") (part "RESISTORR_0603"))
    )
    (comp (ref "R153")
      (value "330")
      (footprint "eagle-import:0603")
      (libsource (lib "eagle-import") (part "RESISTORR_0603"))
    )
    (comp (ref "R154")
      (value "2.2K")
      (footprint "eagle-import:0603")
      (libsource (lib "eagle-import") (part "RESISTORR_0603"))
    )
    (comp (ref "R155")
      (value "2.2K")
      (footprint "eagle-import:0603")
      (libsource (lib "eagle-import") (part "RESISTORR_0603"))
    )
    (comp (ref "R156")
      (value "220")
      (footprint "eagle-import:0603")
      (libsource (lib "eagle-import") (part "RESISTORR_0603"))
    )
    (comp (ref "R157")
      (value "220")
      (footprint "eagle-import:0603")
      (libsource (lib "eagle-import") (part "RESISTORR_0603"))
    )
    (comp (ref "R158")
      (value "390")
      (footprint "eagle-import:0603")
      (libsource (lib "eagle-import") (part "RESISTORR_0603"))
    )
    (comp (ref "R159")
      (value "330")
      (footprint "eagle-import:0603")
      (libsource (lib "eagle-import") (part "RESISTORR_0603"))
    )
    (comp (ref "R160")
      (value "330")
      (footprint "eagle-import:0603")
      (libsource (lib "eagle-import") (part "RESISTORR_0603"))
    )
    (comp (ref "R161")
      (value "0")
      (footprint "eagle-import:0603")
      (libsource (lib "eagle-import") (part "RESISTORR_0603"))
    )
    (comp (ref "R162")
      (value "DNP")
      (footprint "eagle-import:0603")
      (libsource (lib "eagle-import") (part "RESISTORR_0603"))
    )
    (comp (ref "R163")
      (value "DNP")
      (footprint "eagle-import:0603")
      (libsource (lib "eagle-import") (part "RESISTORR_0603"))
    )
    (comp (ref "R164")
      (value "100")
      (footprint "eagle-import:0603")
      (libsource (lib "eagle-import") (part "RESISTORR_0603"))
    )
    (comp (ref "R165")
      (value "100")
      (footprint "eagle-import:0603")
      (libsource (lib "eagle-import") (part "RESISTORR_0603"))
    )
    (comp (ref "R166")
      (value "100")
      (footprint "eagle-import:0603")
      (libsource (lib "eagle-import") (part "RESISTORR_0603"))
    )
    (comp (ref "R167")
      (value "100")
      (footprint "eagle-import:0603")
      (libsource (lib "eagle-import") (part "RESISTORR_0603"))
    )
    (comp (ref "R168")
      (value "100")
      (footprint "eagle-import:0603")
      (libsource (lib "eagle-import") (part "RESISTORR_0603"))
    )
    (comp (ref "R169")
      (value "100")
      (footprint "eagle-import:0603")
      (libsource (lib "eagle-import") (part "RESISTORR_0603"))
    )
    (comp (ref "R170")
      (value "100")
      (footprint "eagle-import:0603")
      (libsource (lib "eagle-import") (part "RESISTORR_0603"))
    )
    (comp (ref "R171")
      (value "100")
      (footprint "eagle-import:0603")
      (libsource (lib "eagle-import") (part "RESISTORR_0603"))
    )
    (comp (ref "R172")
      (value "22")
      (footprint "eagle-import:0603")
      (libsource (lib "eagle-import") (part "RESISTORR_0603"))
    )
    (comp (ref "R173")
      (value "22")
      (footprint "eagle-import:0603")
      (libsource (lib "eagle-import") (part "RESISTORR_0603"))
    )
    (comp (ref "R174")
      (value "100")
      (footprint "eagle-import:0603")
      (libsource (lib "eagle-import") (part "RESISTORR_0603"))
    )
    (comp (ref "R175")
      (value "22")
      (footprint "eagle-import:0603")
      (libsource (lib "eagle-import") (part "RESISTORR_0603"))
    )
    (comp (ref "R176")
      (value "100")
      (footprint "eagle-import:0603")
      (libsource (lib "eagle-import") (part "RESISTORR_0603"))
    )
    (comp (ref "R177")
      (value "22")
      (footprint "eagle-import:0603")
      (libsource (lib "eagle-import") (part "RESISTORR_0603"))
    )
    (comp (ref "R178")
      (value "100")
      (footprint "eagle-import:0603")
      (libsource (lib "eagle-import") (part "RESISTORR_0603"))
    )
    (comp (ref "R179")
      (value "100")
      (footprint "eagle-import:0603")
      (libsource (lib "eagle-import") (part "RESISTORR_0603"))
    )
    (comp (ref "R180")
      (value "100")
      (footprint "eagle-import:0603")
      (libsource (lib "eagle-import") (part "RESISTORR_0603"))
    )
    (comp (ref "R181")
      (value "100")
      (footprint "eagle-import:0603")
      (libsource (lib "eagle-import") (part "RESISTORR_0603"))
    )
    (comp (ref "R182")
      (value "100")
      (footprint "eagle-import:0603")
      (libsource (lib "eagle-import") (part "RESISTORR_0603"))
    )
    (comp (ref "R183")
      (value "DNP")
      (footprint "eagle-import:0603")
      (libsource (lib "eagle-import") (part "RESISTORR_0603"))
    )
    (comp (ref "R184")
      (value "DNP")
      (footprint "eagle-import:0603")
      (libsource (lib "eagle-import") (part "RESISTORR_0603"))
    )
    (comp (ref "R185")
      (value "100")
      (footprint "eagle-import:0603")
      (libsource (lib "eagle-import") (part "RESISTORR_0603"))
    )
    (comp (ref "R186")
      (value "100")
      (footprint "eagle-import:0603")
      (libsource (lib "eagle-import") (part "RESISTORR_0603"))
    )
    (comp (ref "R187")
      (value "100")
      (footprint "eagle-import:0603")
      (libsource (lib "eagle-import") (part "RESISTORR_0603"))
    )
    (comp (ref "R188")
      (value "100")
      (footprint "eagle-import:0603")
      (libsource (lib "eagle-import") (part "RESISTORR_0603"))
    )
    (comp (ref "R189")
      (value "100")
      (footprint "eagle-import:0603")
      (libsource (lib "eagle-import") (part "RESISTORR_0603"))
    )
    (comp (ref "R190")
      (value "2.2K")
      (footprint "eagle-import:0603")
      (libsource (lib "eagle-import") (part "RESISTORR_0603"))
    )
    (comp (ref "R191")
      (value "2.2K")
      (footprint "eagle-import:0603")
      (libsource (lib "eagle-import") (part "RESISTORR_0603"))
    )
    (comp (ref "SW1")
      (value "SW_DIP-2")
      (footprint "eagle-import:DIPSWITCH-02")
      (libsource (lib "eagle-import") (part "SW_DIP-2"))
    )
    (comp (ref "U1")
      (value "MAX4062")
      (footprint "eagle-import:MSOP10")
      (libsource (lib "eagle-import") (part "MAX4062"))
    )
    (comp (ref "U2")
      (value "SN74HCT541SOIC-20")
      (footprint "eagle-import:SOIC-20")
      (libsource (lib "eagle-import") (part "SN74HCT541SOIC-20"))
    )
    (comp (ref "U3")
      (value "LM5002")
      (footprint "eagle-import:SO8")
      (libsource (lib "eagle-import") (part "LM5002"))
    )
    (comp (ref "U4")
      (value "SN74HCT541SOIC-20")
      (footprint "eagle-import:SOIC-20")
      (libsource (lib "eagle-import") (part "SN74HCT541SOIC-20"))
    )
    (comp (ref "U5")
      (value "BLUETOOTH-RN41\"")
      (footprint "eagle-import:RN41")
      (libsource (lib "eagle-import") (part "BLUETOOTH-RN41{dblquote}"))
    )
    (comp (ref "U6")
      (value "ADC128S102")
      (footprint "eagle-import:TSSOP16")
      (libsource (lib "eagle-import") (part "ADC128S102"))
    )
    (comp (ref "U7")
      (value "SN74HCT541SOIC-20")
      (footprint "eagle-import:SOIC-20")
      (libsource (lib "eagle-import") (part "SN74HCT541SOIC-20"))
    )
    (comp (ref "U8")
      (value "6N138SMD8")
      (footprint "eagle-import:SMD-8")
      (libsource (lib "eagle-import") (part "6N138SMD8"))
    )
    (comp (ref "U9")
      (value "FLASH-SPI-25XXSMD1")
      (footprint "eagle-import:SO08-EIAJ")
      (libsource (lib "eagle-import") (part "FLASH-SPI-25XXSMD1"))
    )
    (comp (ref "U10")
      (value "SN74HCT541SOIC-20")
      (footprint "eagle-import:SOIC-20")
      (libsource (lib "eagle-import") (part "SN74HCT541SOIC-20"))
    )
  )
  (nets
    (net (code "1") (name "+3V3") (class "Default")
      (node (ref "C26") (pin "1") (pinfunction "1_1") (pintype "passive"))
      (node (ref "C27") (pin "1") (pinfunction "1_1") (pintype "passive"))
      (node (ref "C28") (pin "1") (pinfunction "1_1") (pintype "passive"))
      (node (ref "C54") (pin "1") (pinfunction "1_1") (pintype "passive"))
      (node (ref "C55") (pin "1") (pinfunction "1_1") (pintype "passive"))
      (node (ref "C68") (pin "1") (pinfunction "1_1") (pintype "passive"))
      (node (ref "C69") (pin "P$1") (pinfunction "1_P$1") (pintype "passive"))
      (node (ref "D1") (pin "C") (pinfunction "C_C") (pintype "passive"))
      (node (ref "D2") (pin "C") (pinfunction "C_C") (pintype "passive"))
      (node (ref "JP1") (pin "W2_3V3") (pinfunction "3V3_W2_3V3") (pintype "passive"))
      (node (ref "JP1") (pin "W3_3V3") (pinfunction "3V3_W3_3V3") (pintype "passive"))
      (node (ref "JP1") (pin "W3_3V3_2") (pinfunction "3V3_W3_3V3_2") (pintype "passive"))
      (node (ref "L2") (pin "1") (pinfunction "1_1") (pintype "passive"))
      (node (ref "R1") (pin "2") (pinfunction "2_2") (pintype "passive"))
      (node (ref "R123") (pin "2") (pinfunction "2_2") (pintype "passive"))
      (node (ref "R157") (pin "2") (pinfunction "2_2") (pintype "passive"))
      (node (ref "R161") (pin "2") (pinfunction "2_2") (pintype "passive"))
      (node (ref "R45") (pin "2") (pinfunction "2_2") (pintype "passive"))
      (node (ref "R57") (pin "2") (pinfunction "2_2") (pintype "passive"))
      (node (ref "R6") (pin "1") (pinfunction "1_1") (pintype "passive"))
      (node (ref "R81") (pin "2") (pinfunction "2_2") (pintype "passive"))
      (node (ref "R82") (pin "2") (pinfunction "2_2") (pintype "passive"))
      (node (ref "R83") (pin "2") (pinfunction "2_2") (pintype "passive"))
      (node (ref "R95") (pin "2") (pinfunction "2_2") (pintype "passive"))
      (node (ref "U1") (pin "P$5") (pinfunction "VCC_P$5") (pintype "bidirectional"))
      (node (ref "U5") (pin "11") (pinfunction "VDD_11") (pintype "bidirectional"))
      (node (ref "U6") (pin "13") (pinfunction "VD_13") (pintype "bidirectional"))
      (node (ref "U8") (pin "P$8") (pinfunction "VCC_P$8") (pintype "passive"))
      (node (ref "U9") (pin "3") (pinfunction "WP_3") (pintype "bidirectional"))
      (node (ref "U9") (pin "7") (pinfunction "HOLD_7") (pintype "bidirectional"))
      (node (ref "U9") (pin "8") (pinfunction "VCC_8") (pintype "bidirectional"))
    )
    (net (code "2") (name "+5V") (class "Default")
      (node (ref "JP1") (pin "W3_5V") (pinfunction "5V0_W3_5V") (pintype "passive"))
      (node (ref "R152") (pin "2") (pinfunction "2_2") (pintype "passive"))
      (node (ref "R153") (pin "2") (pinfunction "2_2") (pintype "passive"))
    )
    (net (code "3") (name "/A0") (class "Default")
      (node (ref "JP1") (pin "A0") (pinfunction "A0_A0") (pintype "bidirectional"))
      (node (ref "R64") (pin "1") (pinfunction "1_1") (pintype "passive"))
      (node (ref "R73") (pin "1") (pinfunction "1_1") (pintype "passive"))
    )
    (net (code "4") (name "/A1") (class "Default")
      (node (ref "JP1") (pin "A1") (pinfunction "A1_A1") (pintype "bidirectional"))
      (node (ref "R65") (pin "1") (pinfunction "1_1") (pintype "passive"))
      (node (ref "R71") (pin "1") (pinfunction "1_1") (pintype "passive"))
    )
    (net (code "5") (name "/A2") (class "Default")
      (node (ref "JP1") (pin "A2") (pinfunction "A2_A2") (pintype "bidirectional"))
      (node (ref "R66") (pin "1") (pinfunction "1_1") (pintype "passive"))
      (node (ref "R69") (pin "1") (pinfunction "1_1") (pintype "passive"))
    )
    (net (code "6") (name "/A3") (class "Default")
      (node (ref "JP1") (pin "A3") (pinfunction "A3_A3") (pintype "bidirectional"))
      (node (ref "R67") (pin "1") (pinfunction "1_1") (pintype "passive"))
      (node (ref "R68") (pin "1") (pinfunction "1_1") (pintype "passive"))
    )
    (net (code "7") (name "/A4") (class "Default")
      (node (ref "JP1") (pin "A4") (pinfunction "A4_A4") (pintype "bidirectional"))
      (node (ref "R38") (pin "1") (pinfunction "1_1") (pintype "passive"))
      (node (ref "R9") (pin "2") (pinfunction "2_2") (pintype "passive"))
    )
    (net (code "8") (name "/A5") (class "Default")
      (node (ref "JP1") (pin "A5") (pinfunction "A5_A5") (pintype "bidirectional"))
      (node (ref "R10") (pin "2") (pinfunction "2_2") (pintype "passive"))
      (node (ref "R34") (pin "1") (pinfunction "1_1") (pintype "passive"))
    )
    (net (code "9") (name "/A6") (class "Default")
      (node (ref "JP1") (pin "A6") (pinfunction "A6_A6") (pintype "bidirectional"))
      (node (ref "R11") (pin "2") (pinfunction "2_2") (pintype "passive"))
      (node (ref "R30") (pin "1") (pinfunction "1_1") (pintype "passive"))
    )
    (net (code "10") (name "/A7") (class "Default")
      (node (ref "JP1") (pin "A7") (pinfunction "A7_A7") (pintype "bidirectional"))
      (node (ref "R12") (pin "2") (pinfunction "2_2") (pintype "passive"))
      (node (ref "R28") (pin "1") (pinfunction "1_1") (pintype "passive"))
    )
    (net (code "11") (name "/A8") (class "Default")
      (node (ref "JP1") (pin "A8") (pinfunction "A8_A8") (pintype "bidirectional"))
      (node (ref "R13") (pin "2") (pinfunction "2_2") (pintype "passive"))
      (node (ref "R26") (pin "1") (pinfunction "1_1") (pintype "passive"))
    )
    (net (code "12") (name "/A9") (class "Default")
      (node (ref "JP1") (pin "A9") (pinfunction "A9_A9") (pintype "bidirectional"))
      (node (ref "R14") (pin "2") (pinfunction "2_2") (pintype "passive"))
      (node (ref "R21") (pin "1") (pinfunction "1_1") (pintype "passive"))
    )
    (net (code "13") (name "/A10") (class "Default")
      (node (ref "JP1") (pin "A10") (pinfunction "A10_A10") (pintype "bidirectional"))
      (node (ref "R15") (pin "2") (pinfunction "2_2") (pintype "passive"))
      (node (ref "R19") (pin "1") (pinfunction "1_1") (pintype "passive"))
    )
    (net (code "14") (name "/A11") (class "Default")
      (node (ref "JP1") (pin "A11") (pinfunction "A11_A11") (pintype "bidirectional"))
      (node (ref "R16") (pin "2") (pinfunction "2_2") (pintype "passive"))
      (node (ref "R18") (pin "1") (pinfunction "1_1") (pintype "passive"))
    )
    (net (code "15") (name "/ADC_CS") (class "Default")
      (node (ref "JP1") (pin "A12") (pinfunction "A12_A12") (pintype "bidirectional"))
      (node (ref "R110") (pin "2") (pinfunction "2_2") (pintype "passive"))
    )
    (net (code "16") (name "/ADC_IN0") (class "Default")
      (node (ref "JP11") (pin "8") (pinfunction "8_8") (pintype "passive"))
      (node (ref "U6") (pin "4") (pinfunction "IN0_4") (pintype "bidirectional"))
    )
    (net (code "17") (name "/ADC_IN1") (class "Default")
      (node (ref "JP11") (pin "7") (pinfunction "7_7") (pintype "passive"))
      (node (ref "U6") (pin "5") (pinfunction "IN1_5") (pintype "bidirectional"))
    )
    (net (code "18") (name "/ADC_IN2") (class "Default")
      (node (ref "JP11") (pin "6") (pinfunction "6_6") (pintype "passive"))
      (node (ref "U6") (pin "6") (pinfunction "IN2_6") (pintype "bidirectional"))
    )
    (net (code "19") (name "/ADC_IN3") (class "Default")
      (node (ref "JP11") (pin "5") (pinfunction "5_5") (pintype "passive"))
      (node (ref "U6") (pin "7") (pinfunction "IN3_7") (pintype "bidirectional"))
    )
    (net (code "20") (name "/ADC_IN4") (class "Default")
      (node (ref "C58") (pin "2") (pinfunction "2_2") (pintype "passive"))
      (node (ref "R114") (pin "2") (pinfunction "2_2") (pintype "passive"))
      (node (ref "R95") (pin "1") (pinfunction "1_1") (pintype "passive"))
      (node (ref "U6") (pin "8") (pinfunction "IN4_8") (pintype "bidirectional"))
    )
    (net (code "21") (name "/ADC_IN5") (class "Default")
      (node (ref "C57") (pin "2") (pinfunction "2_2") (pintype "passive"))
      (node (ref "JP11") (pin "3") (pinfunction "3_3") (pintype "passive"))
      (node (ref "R116") (pin "2") (pinfunction "2_2") (pintype "passive"))
      (node (ref "R96") (pin "1") (pinfunction "1_1") (pintype "passive"))
      (node (ref "U6") (pin "9") (pinfunction "IN5_9") (pintype "bidirectional"))
    )
    (net (code "22") (name "/ADC_IN6") (class "Default")
      (node (ref "C59") (pin "2") (pinfunction "2_2") (pintype "passive"))
      (node (ref "R118") (pin "2") (pinfunction "2_2") (pintype "passive"))
      (node (ref "R98") (pin "1") (pinfunction "1_1") (pintype "passive"))
      (node (ref "U6") (pin "10") (pinfunction "IN6_10") (pintype "bidirectional"))
    )
    (net (code "23") (name "/ADC_IN7") (class "Default")
      (node (ref "C60") (pin "2") (pinfunction "2_2") (pintype "passive"))
      (node (ref "R100") (pin "1") (pinfunction "1_1") (pintype "passive"))
      (node (ref "R120") (pin "2") (pinfunction "2_2") (pintype "passive"))
      (node (ref "U6") (pin "11") (pinfunction "IN7_11") (pintype "bidirectional"))
    )
    (net (code "24") (name "/ADC_MISO") (class "Default")
      (node (ref "JP1") (pin "A14") (pinfunction "A14_A14") (pintype "bidirectional"))
      (node (ref "R108") (pin "2") (pinfunction "2_2") (pintype "passive"))
    )
    (net (code "25") (name "/ADC_MOSI") (class "Default")
      (node (ref "JP1") (pin "A13") (pinfunction "A13_A13") (pintype "bidirectional"))
      (node (ref "R106") (pin "2") (pinfunction "2_2") (pintype "passive"))
    )
    (net (code "26") (name "/ADC_SCK") (class "Default")
      (node (ref "JP1") (pin "A15") (pinfunction "A15_A15") (pintype "bidirectional"))
      (node (ref "R104") (pin "2") (pinfunction "2_2") (pintype "passive"))
    )
    (net (code "27") (name "/AIN_4") (class "Default")
      (node (ref "C58") (pin "1") (pinfunction "1_1") (pintype "passive"))
      (node (ref "JP11") (pin "4") (pinfunction "4_4") (pintype "passive"))
      (node (ref "R113") (pin "2") (pinfunction "2_2") (pintype "passive"))
      (node (ref "R94") (pin "1") (pinfunction "1_1") (pintype "passive"))
    )
    (net (code "28") (name "/AUX_SEL") (class "Default")
      (node (ref "R17") (pin "2") (pinfunction "2_2") (pintype "passive"))
      (node (ref "SW1") (pin "4") (pinfunction "4_4") (pintype "passive"))
      (node (ref "U1") (pin "P$2") (pinfunction "INT/AUX_P$2") (pintype "bidirectional"))
    )
    (net (code "29") (name "/B4") (class "Default")
      (node (ref "JP1") (pin "B4") (pinfunction "B4_B4") (pintype "bidirectional"))
      (node (ref "R126") (pin "1") (pinfunction "1_1") (pintype "passive"))
      (node (ref "R149") (pin "1") (pinfunction "1_1") (pintype "passive"))
    )
    (net (code "30") (name "/B5") (class "Default")
      (node (ref "JP1") (pin "B5") (pinfunction "B5_B5") (pintype "bidirectional"))
      (node (ref "R127") (pin "1") (pinfunction "1_1") (pintype "passive"))
      (node (ref "R147") (pin "1") (pinfunction "1_1") (pintype "passive"))
    )
    (net (code "31") (name "/B6") (class "Default")
      (node (ref "JP1") (pin "B6") (pinfunction "B6_B6") (pintype "bidirectional"))
      (node (ref "R128") (pin "1") (pinfunction "1_1") (pintype "passive"))
      (node (ref "R143") (pin "1") (pinfunction "1_1") (pintype "passive"))
    )
    (net (code "32") (name "/B7") (class "Default")
      (node (ref "JP1") (pin "B7") (pinfunction "B7_B7") (pintype "bidirectional"))
      (node (ref "R129") (pin "1") (pinfunction "1_1") (pintype "passive"))
      (node (ref "R141") (pin "1") (pinfunction "1_1") (pintype "passive"))
    )
    (net (code "33") (name "/B8") (class "Default")
      (node (ref "JP1") (pin "B8") (pinfunction "B8_B8") (pintype "bidirectional"))
      (node (ref "R130") (pin "1") (pinfunction "1_1") (pintype "passive"))
      (node (ref "R139") (pin "1") (pinfunction "1_1") (pintype "passive"))
    )
    (net (code "34") (name "/B9") (class "Default")
      (node (ref "JP1") (pin "B9") (pinfunction "B9_B9") (pintype "bidirectional"))
      (node (ref "R131") (pin "1") (pinfunction "1_1") (pintype "passive"))
      (node (ref "R137") (pin "1") (pinfunction "1_1") (pintype "passive"))
    )
    (net (code "35") (name "/B10") (class "Default")
      (node (ref "JP1") (pin "B10") (pinfunction "B10_B10") (pintype "bidirectional"))
      (node (ref "R132") (pin "1") (pinfunction "1_1") (pintype "passive"))
      (node (ref "R135") (pin "1") (pinfunction "1_1") (pintype "passive"))
    )
    (net (code "36") (name "/B11") (class "Default")
      (node (ref "JP1") (pin "B11") (pinfunction "B11_B11") (pintype "bidirectional"))
      (node (ref "R133") (pin "1") (pinfunction "1_1") (pintype "passive"))
      (node (ref "R134") (pin "1") (pinfunction "1_1") (pintype "passive"))
    )
    (net (code "37") (name "/B12") (class "Default")
      (node (ref "JP1") (pin "B12") (pinfunction "B12_B12") (pintype "bidirectional"))
      (node (ref "R60") (pin "1") (pinfunction "1_1") (pintype "passive"))
      (node (ref "R86") (pin "1") (pinfunction "1_1") (pintype "passive"))
    )
    (net (code "38") (name "/B13") (class "Default")
      (node (ref "JP1") (pin "B13") (pinfunction "B13_B13") (pintype "bidirectional"))
      (node (ref "R61") (pin "1") (pinfunction "1_1") (pintype "passive"))
      (node (ref "R84") (pin "1") (pinfunction "1_1") (pintype "passive"))
    )
    (net (code "39") (name "/B14") (class "Default")
      (node (ref "JP1") (pin "B14") (pinfunction "B14_B14") (pintype "bidirectional"))
      (node (ref "R62") (pin "1") (pinfunction "1_1") (pintype "passive"))
      (node (ref "R77") (pin "1") (pinfunction "1_1") (pintype "passive"))
    )
    (net (code "40") (name "/B15") (class "Default")
      (node (ref "JP1") (pin "B15") (pinfunction "B15_B15") (pintype "bidirectional"))
      (node (ref "R63") (pin "1") (pinfunction "1_1") (pintype "passive"))
      (node (ref "R75") (pin "1") (pinfunction "1_1") (pintype "passive"))
    )
    (net (code "41") (name "/C0") (class "Default")
      (node (ref "JP1") (pin "C0") (pinfunction "C0_C0") (pintype "bidirectional"))
      (node (ref "R107") (pin "2") (pinfunction "2_2") (pintype "passive"))
    )
    (net (code "42") (name "/C1") (class "Default")
      (node (ref "JP1") (pin "C1") (pinfunction "C1_C1") (pintype "bidirectional"))
      (node (ref "R105") (pin "2") (pinfunction "2_2") (pintype "passive"))
    )
    (net (code "43") (name "/C2") (class "Default")
      (node (ref "JP1") (pin "C2") (pinfunction "C2_C2") (pintype "bidirectional"))
      (node (ref "R103") (pin "2") (pinfunction "2_2") (pintype "passive"))
    )
    (net (code "44") (name "/C3") (class "Default")
      (node (ref "JP1") (pin "C3") (pinfunction "C3_C3") (pintype "bidirectional"))
      (node (ref "R102") (pin "2") (pinfunction "2_2") (pintype "passive"))
    )
    (net (code "45") (name "/C4") (class "Default")
      (node (ref "JP1") (pin "C4") (pinfunction "C4_C4") (pintype "bidirectional"))
      (node (ref "R101") (pin "2") (pinfunction "2_2") (pintype "passive"))
      (node (ref "R158") (pin "2") (pinfunction "2_2") (pintype "passive"))
    )
    (net (code "46") (name "/C5") (class "Default")
      (node (ref "JP1") (pin "C5") (pinfunction "C5_C5") (pintype "bidirectional"))
      (node (ref "R91") (pin "2") (pinfunction "2_2") (pintype "passive"))
    )
    (net (code "47") (name "/C6") (class "Default")
      (node (ref "JP1") (pin "C6") (pinfunction "C6_C6") (pintype "bidirectional"))
      (node (ref "R90") (pin "2") (pinfunction "2_2") (pintype "passive"))
    )
    (net (code "48") (name "/C7") (class "Default")
      (node (ref "JP1") (pin "C7") (pinfunction "C7_C7") (pintype "bidirectional"))
      (node (ref "R89") (pin "2") (pinfunction "2_2") (pintype "passive"))
    )
    (net (code "49") (name "/C8") (class "Default")
      (node (ref "JP1") (pin "C8") (pinfunction "C8_C8") (pintype "bidirectional"))
      (node (ref "R164") (pin "1") (pinfunction "1_1") (pintype "passive"))
      (node (ref "R187") (pin "1") (pinfunction "1_1") (pintype "passive"))
    )
    (net (code "50") (name "/C9") (class "Default")
      (node (ref "JP1") (pin "C9") (pinfunction "C9_C9") (pintype "bidirectional"))
      (node (ref "R165") (pin "1") (pinfunction "1_1") (pintype "passive"))
      (node (ref "R185") (pin "1") (pinfunction "1_1") (pintype "passive"))
    )
    (net (code "51") (name "/C10") (class "Default")
      (node (ref "JP1") (pin "C10") (pinfunction "C10_C10") (pintype "bidirectional"))
      (node (ref "R166") (pin "1") (pinfunction "1_1") (pintype "passive"))
      (node (ref "R181") (pin "1") (pinfunction "1_1") (pintype "passive"))
    )
    (net (code "52") (name "/C11") (class "Default")
      (node (ref "JP1") (pin "C11") (pinfunction "C11_C11") (pintype "bidirectional"))
      (node (ref "R167") (pin "1") (pinfunction "1_1") (pintype "passive"))
      (node (ref "R179") (pin "1") (pinfunction "1_1") (pintype "passive"))
    )
    (net (code "53") (name "/C12") (class "Default")
      (node (ref "JP1") (pin "C12") (pinfunction "C12_C12") (pintype "bidirectional"))
      (node (ref "R168") (pin "1") (pinfunction "1_1") (pintype "passive"))
      (node (ref "R177") (pin "1") (pinfunction "1_1") (pintype "passive"))
    )
    (net (code "54") (name "/C13") (class "Default")
      (node (ref "JP1") (pin "C13") (pinfunction "C13_C13") (pintype "bidirectional"))
      (node (ref "R169") (pin "1") (pinfunction "1_1") (pintype "passive"))
      (node (ref "R175") (pin "1") (pinfunction "1_1") (pintype "passive"))
    )
    (net (code "55") (name "/C14") (class "Default")
      (node (ref "JP1") (pin "C14") (pinfunction "C14_C14") (pintype "bidirectional"))
      (node (ref "R170") (pin "1") (pinfunction "1_1") (pintype "passive"))
      (node (ref "R173") (pin "1") (pinfunction "1_1") (pintype "passive"))
    )
    (net (code "56") (name "/C15") (class "Default")
      (node (ref "JP1") (pin "C15") (pinfunction "C15_C15") (pintype "bidirectional"))
      (node (ref "R171") (pin "1") (pinfunction "1_1") (pintype "passive"))
      (node (ref "R172") (pin "1") (pinfunction "1_1") (pintype "passive"))
    )
    (net (code "57") (name "/FLASH_CS") (class "Default")
      (node (ref "JP1") (pin "B0") (pinfunction "B0_B0") (pintype "bidirectional"))
      (node (ref "U9") (pin "1") (pinfunction "CS_1") (pintype "bidirectional"))
    )
    (net (code "58") (name "/FLASH_MISO") (class "Default")
      (node (ref "JP1") (pin "B1") (pinfunction "B1_B1") (pintype "bidirectional"))
      (node (ref "U9") (pin "2") (pinfunction "MISO_2") (pintype "bidirectional"))
    )
    (net (code "59") (name "/FLASH_MOSI") (class "Default")
      (node (ref "JP1") (pin "B3") (pinfunction "B3_B3") (pintype "bidirectional"))
      (node (ref "U9") (pin "5") (pinfunction "MOSI_5") (pintype "bidirectional"))
    )
    (net (code "60") (name "/FLASH_SCK") (class "Default")
      (node (ref "JP1") (pin "B2") (pinfunction "B2_B2") (pintype "bidirectional"))
      (node (ref "U9") (pin "6") (pinfunction "SCK_6") (pintype "bidirectional"))
    )
    (net (code "61") (name "/LM5002_EN") (class "Default")
      (node (ref "R3") (pin "2") (pinfunction "2_2") (pintype "passive"))
      (node (ref "R40") (pin "1") (pinfunction "1_1") (pintype "passive"))
      (node (ref "R50") (pin "2") (pinfunction "2_2") (pintype "passive"))
      (node (ref "U3") (pin "8") (pinfunction "EN_8") (pintype "bidirectional"))
    )
    (net (code "62") (name "/MAX4062_OUT") (class "Default")
      (node (ref "C57") (pin "1") (pinfunction "1_1") (pintype "passive"))
      (node (ref "R115") (pin "2") (pinfunction "2_2") (pintype "passive"))
      (node (ref "U1") (pin "P$3") (pinfunction "OUT_P$3") (pintype "bidirectional"))
    )
    (net (code "63") (name "/RG1") (class "Default")
      (node (ref "R4") (pin "3") (pinfunction "E_3") (pintype "passive"))
      (node (ref "R8") (pin "2") (pinfunction "2_2") (pintype "passive"))
      (node (ref "U1") (pin "P$10") (pinfunction "G1_P$10") (pintype "bidirectional"))
    )
    (net (code "64") (name "/RG2") (class "Default")
      (node (ref "R4") (pin "2") (pinfunction "S_2") (pintype "passive"))
      (node (ref "R8") (pin "1") (pinfunction "1_1") (pintype "passive"))
      (node (ref "U1") (pin "P$1") (pinfunction "G2_P$1") (pintype "bidirectional"))
    )
    (net (code "65") (name "/VBIAS") (class "Default")
      (node (ref "C24") (pin "1") (pinfunction "1_1") (pintype "passive"))
      (node (ref "R2") (pin "2") (pinfunction "2_2") (pintype "passive"))
      (node (ref "R25") (pin "2") (pinfunction "2_2") (pintype "passive"))
      (node (ref "U1") (pin "P$4") (pinfunction "BIAS_P$4") (pintype "bidirectional"))
    )
    (net (code "66") (name "GND") (class "Default")
      (node (ref "C1") (pin "-") (pinfunction "-_-") (pintype "passive"))
      (node (ref "C10") (pin "P$2") (pinfunction "2_P$2") (pintype "passive"))
      (node (ref "C11") (pin "P$2") (pinfunction "2_P$2") (pintype "passive"))
      (node (ref "C12") (pin "P$2") (pinfunction "2_P$2") (pintype "passive"))
      (node (ref "C13") (pin "P$2") (pinfunction "2_P$2") (pintype "passive"))
      (node (ref "C14") (pin "P$2") (pinfunction "2_P$2") (pintype "passive"))
      (node (ref "C15") (pin "P$2") (pinfunction "2_P$2") (pintype "passive"))
      (node (ref "C16") (pin "P$2") (pinfunction "2_P$2") (pintype "passive"))
      (node (ref "C17") (pin "P$2") (pinfunction "2_P$2") (pintype "passive"))
      (node (ref "C18") (pin "P$2") (pinfunction "2_P$2") (pintype "passive"))
      (node (ref "C19") (pin "P$2") (pinfunction "2_P$2") (pintype "passive"))
      (node (ref "C2") (pin "-") (pinfunction "-_-") (pintype "passive"))
      (node (ref "C20") (pin "P$2") (pinfunction "2_P$2") (pintype "passive"))
      (node (ref "C21") (pin "P$2") (pinfunction "2_P$2") (pintype "passive"))
      (node (ref "C22") (pin "P$2") (pinfunction "2_P$2") (pintype "passive"))
      (node (ref "C23") (pin "2") (pinfunction "2_2") (pintype "passive"))
      (node (ref "C24") (pin "2") (pinfunction "2_2") (pintype "passive"))
      (node (ref "C26") (pin "2") (pinfunction "2_2") (pintype "passive"))
      (node (ref "C27") (pin "2") (pinfunction "2_2") (pintype "passive"))
      (node (ref "C28") (pin "2") (pinfunction "2_2") (pintype "passive"))
      (node (ref "C29") (pin "P$2") (pinfunction "2_P$2") (pintype "passive"))
      (node (ref "C3") (pin "-") (pinfunction "-_-") (pintype "passive"))
      (node (ref "C30") (pin "2") (pinfunction "2_2") (pintype "passive"))
      (node (ref "C31") (pin "P$1") (pinfunction "1_P$1") (pintype "passive"))
      (node (ref "C36") (pin "2") (pinfunction "2_2") (pintype "passive"))
      (node (ref "C37") (pin "P$2") (pinfunction "2_P$2") (pintype "passive"))
      (node (ref "C38") (pin "P$2") (pinfunction "2_P$2") (pintype "passive"))
      (node (ref "C39") (pin "P$2") (pinfunction "2_P$2") (pintype "passive"))
      (node (ref "C4") (pin "-") (pinfunction "-_-") (pintype "passive"))
      (node (ref "C40") (pin "P$2") (pinfunction "2_P$2") (pintype "passive"))
      (node (ref "C41") (pin "P$2") (pinfunction "2_P$2") (pintype "passive"))
      (node (ref "C42") (pin "2") (pinfunction "2_2") (pintype "passive"))
      (node (ref "C43") (pin "P$1") (pinfunction "1_P$1") (pintype "passive"))
      (node (ref "C45") (pin "2") (pinfunction "2_2") (pintype "passive"))
      (node (ref "C47") (pin "P$1") (pinfunction "1_P$1") (pintype "passive"))
      (node (ref "C48") (pin "P$1") (pinfunction "1_P$1") (pintype "passive"))
      (node (ref "C49") (pin "P$2") (pinfunction "2_P$2") (pintype "passive"))
      (node (ref "C5") (pin "P$2") (pinfunction "2_P$2") (pintype "passive"))
      (node (ref "C50") (pin "2") (pinfunction "2_2") (pintype "passive"))
      (node (ref "C51") (pin "P$1") (pinfunction "1_P$1") (pintype "passive"))
      (node (ref "C52") (pin "2") (pinfunction "2_2") (pintype "passive"))
      (node (ref "C53") (pin "2") (pinfunction "2_2") (pintype "passive"))
      (node (ref "C54") (pin "2") (pinfunction "2_2") (pintype "passive"))
      (node (ref "C55") (pin "2") (pinfunction "2_2") (pintype "passive"))
      (node (ref "C56") (pin "P$1") (pinfunction "1_P$1") (pintype "passive"))
      (node (ref "C6") (pin "P$2") (pinfunction "2_P$2") (pintype "passive"))
      (node (ref "C61") (pin "P$1") (pinfunction "1_P$1") (pintype "passive"))
      (node (ref "C62") (pin "P$1") (pinfunction "1_P$1") (pintype "passive"))
      (node (ref "C63") (pin "P$2") (pinfunction "2_P$2") (pintype "passive"))
      (node (ref "C64") (pin "2") (pinfunction "2_2") (pintype "passive"))
      (node (ref "C65") (pin "P$1") (pinfunction "1_P$1") (pintype "passive"))
      (node (ref "C66") (pin "P$1") (pinfunction "1_P$1") (pintype "passive"))
      (node (ref "C67") (pin "P$1") (pinfunction "1_P$1") (pintype "passive"))
      (node (ref "C68") (pin "2") (pinfunction "2_2") (pintype "passive"))
      (node (ref "C69") (pin "P$2") (pinfunction "2_P$2") (pintype "passive"))
      (node (ref "C7") (pin "P$2") (pinfunction "2_P$2") (pintype "passive"))
      (node (ref "C70") (pin "P$1") (pinfunction "1_P$1") (pintype "passive"))
      (node (ref "C71") (pin "P$2") (pinfunction "2_P$2") (pintype "passive"))
      (node (ref "C72") (pin "2") (pinfunction "2_2") (pintype "passive"))
      (node (ref "C73") (pin "P$1") (pinfunction "1_P$1") (pintype "passive"))
      (node (ref "C74") (pin "P$1") (pinfunction "1_P$1") (pintype "passive"))
      (node (ref "C75") (pin "P$1") (pinfunction "1_P$1") (pintype "passive"))
      (node (ref "C76") (pin "P$1") (pinfunction "1_P$1") (pintype "passive"))
      (node (ref "C8") (pin "P$2") (pinfunction "2_P$2") (pintype "passive"))
      (node (ref "C9") (pin "P$2") (pinfunction "2_P$2") (pintype "passive"))
      (node (ref "D4") (pin "C") (pinfunction "C_C") (pintype "passive"))
      (node (ref "D5") (pin "C") (pinfunction "C_C") (pintype "passive"))
      (node (ref "D6") (pin "C") (pinfunction "C_C") (pintype "passive"))
      (node (ref "D7") (pin "A") (pinfunction "A_A") (pintype "passive"))
      (node (ref "D8") (pin "A") (pinfunction "A_A") (pintype "passive"))
      (node (ref "J1") (pin "GNDBREAK") (pinfunction "GNDBREAK_GNDBREAK") (pintype "bidirectional"))
      (node (ref "JP1") (pin "W2_GND") (pinfunction "GND_W2_GND") (pintype "power_in"))
      (node (ref "JP1") (pin "W2_GND_2") (pinfunction "GND_W2_GND_2") (pintype "power_in"))
      (node (ref "JP1") (pin "W2_GND_3") (pinfunction "GND_W2_GND_3") (pintype "power_in"))
      (node (ref "JP1") (pin "W2_GND_4") (pinfunction "GND_W2_GND_4") (pintype "power_in"))
      (node (ref "JP1") (pin "W3_GND") (pinfunction "GND_W3_GND") (pintype "power_in"))
      (node (ref "JP1") (pin "W3_GND_2") (pinfunction "GND_W3_GND_2") (pintype "power_in"))
      (node (ref "JP10") (pin "1") (pinfunction "1_1") (pintype "passive"))
      (node (ref "JP12") (pin "1") (pinfunction "1_1") (pintype "passive"))
      (node (ref "JP13") (pin "1") (pinfunction "1_1") (pintype "passive"))
      (node (ref "JP14") (pin "SLEEVE") (pinfunction "SLEEVE_SLEEVE") (pintype "bidirectional"))
      (node (ref "JP15") (pin "1") (pinfunction "1_1") (pintype "passive"))
      (node (ref "JP16") (pin "1") (pinfunction "1_1") (pintype "passive"))
      (node (ref "JP18") (pin "1") (pinfunction "1_1") (pintype "passive"))
      (node (ref "JP19") (pin "1") (pinfunction "1_1") (pintype "passive"))
      (node (ref "JP20") (pin "1") (pinfunction "1_1") (pintype "passive"))
      (node (ref "JP21") (pin "1") (pinfunction "1_1") (pintype "passive"))
      (node (ref "JP22") (pin "1") (pinfunction "1_1") (pintype "passive"))
      (node (ref "JP23") (pin "1") (pinfunction "1_1") (pintype "passive"))
      (node (ref "JP3") (pin "1") (pinfunction "1_1") (pintype "passive"))
      (node (ref "JP5") (pin "SLEEVE") (pinfunction "SLEEVE_SLEEVE") (pintype "bidirectional"))
      (node (ref "JP6") (pin "1") (pinfunction "1_1") (pintype "passive"))
      (node (ref "JP7") (pin "1") (pinfunction "1_1") (pintype "passive"))
      (node (ref "JP8") (pin "1") (pinfunction "1_1") (pintype "passive"))
      (node (ref "JP9") (pin "1") (pinfunction "1_1") (pintype "passive"))
      (node (ref "R109") (pin "1") (pinfunction "1_1") (pintype "passive"))
      (node (ref "R113") (pin "1") (pinfunction "1_1") (pintype "passive"))
      (node (ref "R114") (pin "1") (pinfunction "1_1") (pintype "passive"))
      (node (ref "R115") (pin "1") (pinfunction "1_1") (pintype "passive"))
      (node (ref "R116") (pin "1") (pinfunction "1_1") (pintype "passive"))
      (node (ref "R117") (pin "1") (pinfunction "1_1") (pintype "passive"))
      (node (ref "R118") (pin "1") (pinfunction "1_1") (pintype "passive"))
      (node (ref "R119") (pin "1") (pinfunction "1_1") (pintype "passive"))
      (node (ref "R120") (pin "1") (pinfunction "1_1") (pintype "passive"))
      (node (ref "R121") (pin "1") (pinfunction "1_1") (pintype "passive"))
      (node (ref "R122") (pin "1") (pinfunction "1_1") (pintype "passive"))
      (node (ref "R125") (pin "2") (pinfunction "2_2") (pintype "passive"))
      (node (ref "R154") (pin "1") (pinfunction "1_1") (pintype "passive"))
      (node (ref "R155") (pin "1") (pinfunction "1_1") (pintype "passive"))
      (node (ref "R159") (pin "1") (pinfunction "1_1") (pintype "passive"))
      (node (ref "R160") (pin "1") (pinfunction "1_1") (pintype "passive"))
      (node (ref "R163") (pin "2") (pinfunction "2_2") (pintype "passive"))
      (node (ref "R17") (pin "1") (pinfunction "1_1") (pintype "passive"))
      (node (ref "R190") (pin "1") (pinfunction "1_1") (pintype "passive"))
      (node (ref "R191") (pin "1") (pinfunction "1_1") (pintype "passive"))
      (node (ref "R46") (pin "1") (pinfunction "1_1") (pintype "passive"))
      (node (ref "R47") (pin "1") (pinfunction "1_1") (pintype "passive"))
      (node (ref "R50") (pin "1") (pinfunction "1_1") (pintype "passive"))
      (node (ref "R51") (pin "1") (pinfunction "1_1") (pintype "passive"))
      (node (ref "R52") (pin "1") (pinfunction "1_1") (pintype "passive"))
      (node (ref "R55") (pin "1") (pinfunction "1_1") (pintype "passive"))
      (node (ref "R56") (pin "1") (pinfunction "1_1") (pintype "passive"))
      (node (ref "R59") (pin "2") (pinfunction "2_2") (pintype "passive"))
      (node (ref "R7") (pin "1") (pinfunction "1_1") (pintype "passive"))
      (node (ref "R92") (pin "1") (pinfunction "1_1") (pintype "passive"))
      (node (ref "R93") (pin "1") (pinfunction "1_1") (pintype "passive"))
      (node (ref "SW1") (pin "3") (pinfunction "3_3") (pintype "passive"))
      (node (ref "U1") (pin "P$8") (pinfunction "GND_P$8") (pintype "bidirectional"))
      (node (ref "U10") (pin "10") (pinfunction "GND_10") (pintype "bidirectional"))
      (node (ref "U2") (pin "10") (pinfunction "GND_10") (pintype "bidirectional"))
      (node (ref "U3") (pin "4") (pinfunction "GND_4") (pintype "bidirectional"))
      (node (ref "U4") (pin "10") (pinfunction "GND_10") (pintype "bidirectional"))
      (node (ref "U5") (pin "1") (pinfunction "GND_1") (pintype "bidirectional"))
      (node (ref "U5") (pin "12") (pinfunction "GND1_12") (pintype "bidirectional"))
      (node (ref "U5") (pin "25") (pinfunction "GND2_25") (pintype "bidirectional"))
      (node (ref "U5") (pin "27") (pinfunction "GND3_27") (pintype "bidirectional"))
      (node (ref "U5") (pin "28") (pinfunction "GND4_28") (pintype "bidirectional"))
      (node (ref "U5") (pin "29") (pinfunction "GND5_29") (pintype "bidirectional"))
      (node (ref "U6") (pin "12") (pinfunction "DGND_12") (pintype "bidirectional"))
      (node (ref "U6") (pin "3") (pinfunction "AGND_3") (pintype "bidirectional"))
      (node (ref "U7") (pin "10") (pinfunction "GND_10") (pintype "bidirectional"))
      (node (ref "U8") (pin "P$5") (pinfunction "GND_P$5") (pintype "passive"))
      (node (ref "U9") (pin "4") (pinfunction "GND_4") (pintype "bidirectional"))
    )
    (net (code "67") (name "Net-(C25-Pad1)") (class "Default")
      (node (ref "C25") (pin "1") (pinfunction "1_1") (pintype "passive"))
      (node (ref "JP2") (pin "1") (pinfunction "1_1") (pintype "passive"))
    )
    (net (code "68") (name "Net-(C32-1)") (class "Default")
      (node (ref "C32") (pin "P$1") (pinfunction "1_P$1") (pintype "passive"))
      (node (ref "R25") (pin "1") (pinfunction "1_1") (pintype "passive"))
      (node (ref "R36") (pin "2") (pinfunction "2_2") (pintype "passive"))
    )
    (net (code "69") (name "Net-(C32-2)") (class "Default")
      (node (ref "C32") (pin "P$2") (pinfunction "2_P$2") (pintype "passive"))
      (node (ref "R37") (pin "1") (pinfunction "1_1") (pintype "passive"))
    )
    (net (code "70") (name "Net-(C33-Pad1)") (class "Default")
      (node (ref "C33") (pin "1") (pinfunction "1_1") (pintype "passive"))
      (node (ref "JP5") (pin "RING") (pinfunction "RING_RING") (pintype "bidirectional"))
      (node (ref "R24") (pin "1") (pinfunction "1_1") (pintype "passive"))
      (node (ref "R36") (pin "1") (pinfunction "1_1") (pintype "passive"))
    )
    (net (code "71") (name "Net-(C33-Pad2)") (class "Default")
      (node (ref "C33") (pin "2") (pinfunction "2_2") (pintype "passive"))
      (node (ref "C44") (pin "1") (pinfunction "1_1") (pintype "passive"))
    )
    (net (code "72") (name "Net-(C35-Pad2)") (class "Default")
      (node (ref "C35") (pin "2") (pinfunction "2_2") (pintype "passive"))
      (node (ref "R49") (pin "1") (pinfunction "1_1") (pintype "passive"))
    )
    (net (code "73") (name "Net-(C44-Pad2)") (class "Default")
      (node (ref "C44") (pin "2") (pinfunction "2_2") (pintype "passive"))
      (node (ref "JP5") (pin "TIP") (pinfunction "TIP_TIP") (pintype "bidirectional"))
      (node (ref "R23") (pin "1") (pinfunction "1_1") (pintype "passive"))
      (node (ref "R53") (pin "1") (pinfunction "1_1") (pintype "passive"))
    )
    (net (code "74") (name "Net-(C46-1)") (class "Default")
      (node (ref "C46") (pin "P$1") (pinfunction "1_P$1") (pintype "passive"))
      (node (ref "R53") (pin "2") (pinfunction "2_2") (pintype "passive"))
    )
    (net (code "75") (name "Net-(C46-2)") (class "Default")
      (node (ref "C46") (pin "P$2") (pinfunction "2_P$2") (pintype "passive"))
      (node (ref "R54") (pin "1") (pinfunction "1_1") (pintype "passive"))
    )
    (net (code "76") (name "Net-(C59-Pad1)") (class "Default")
      (node (ref "C59") (pin "1") (pinfunction "1_1") (pintype "passive"))
      (node (ref "R111") (pin "2") (pinfunction "2_2") (pintype "passive"))
      (node (ref "R117") (pin "2") (pinfunction "2_2") (pintype "passive"))
      (node (ref "R97") (pin "1") (pinfunction "1_1") (pintype "passive"))
    )
    (net (code "77") (name "Net-(C60-Pad1)") (class "Default")
      (node (ref "C60") (pin "1") (pinfunction "1_1") (pintype "passive"))
      (node (ref "R112") (pin "2") (pinfunction "2_2") (pintype "passive"))
      (node (ref "R119") (pin "2") (pinfunction "2_2") (pintype "passive"))
      (node (ref "R99") (pin "1") (pinfunction "1_1") (pintype "passive"))
    )
    (net (code "78") (name "Net-(D4-PadA)") (class "Default")
      (node (ref "D4") (pin "A") (pinfunction "A_A") (pintype "passive"))
      (node (ref "R43") (pin "1") (pinfunction "1_1") (pintype "passive"))
    )
    (net (code "79") (name "Net-(D5-PadA)") (class "Default")
      (node (ref "D5") (pin "A") (pinfunction "A_A") (pintype "passive"))
      (node (ref "R44") (pin "1") (pinfunction "1_1") (pintype "passive"))
    )
    (net (code "80") (name "Net-(D6-PadA)") (class "Default")
      (node (ref "D6") (pin "A") (pinfunction "A_A") (pintype "passive"))
      (node (ref "R45") (pin "1") (pinfunction "1_1") (pintype "passive"))
    )
    (net (code "81") (name "Net-(D9-A)") (class "Default")
      (node (ref "D9") (pin "1") (pinfunction "A_1") (pintype "passive"))
      (node (ref "U5") (pin "21") (pinfunction "PIO5_21") (pintype "bidirectional"))
    )
    (net (code "82") (name "Net-(D9-C)") (class "Default")
      (node (ref "D9") (pin "2") (pinfunction "C_2") (pintype "passive"))
      (node (ref "R121") (pin "2") (pinfunction "2_2") (pintype "passive"))
    )
    (net (code "83") (name "Net-(D10-A)") (class "Default")
      (node (ref "D10") (pin "1") (pinfunction "A_1") (pintype "passive"))
      (node (ref "U5") (pin "19") (pinfunction "PIO2_19") (pintype "bidirectional"))
    )
    (net (code "84") (name "Net-(D10-C)") (class "Default")
      (node (ref "D10") (pin "2") (pinfunction "C_2") (pintype "passive"))
      (node (ref "R122") (pin "2") (pinfunction "2_2") (pintype "passive"))
    )
    (net (code "85") (name "Net-(JP2-Pad2)") (class "Default")
      (node (ref "JP2") (pin "2") (pinfunction "2_2") (pintype "passive"))
      (node (ref "R2") (pin "1") (pinfunction "1_1") (pintype "passive"))
    )
    (net (code "86") (name "Net-(JP3-Pad2)") (class "Default")
      (node (ref "JP3") (pin "2") (pinfunction "2_2") (pintype "passive"))
      (node (ref "R20") (pin "2") (pinfunction "2_2") (pintype "passive"))
    )
    (net (code "87") (name "Net-(JP3-Pad3)") (class "Default")
      (node (ref "JP3") (pin "3") (pinfunction "3_3") (pintype "passive"))
      (node (ref "R22") (pin "2") (pinfunction "2_2") (pintype "passive"))
    )
    (net (code "88") (name "Net-(JP6-Pad2)") (class "Default")
      (node (ref "JP6") (pin "2") (pinfunction "2_2") (pintype "passive"))
      (node (ref "R27") (pin "2") (pinfunction "2_2") (pintype "passive"))
    )
    (net (code "89") (name "Net-(JP6-Pad3)") (class "Default")
      (node (ref "JP6") (pin "3") (pinfunction "3_3") (pintype "passive"))
      (node (ref "R29") (pin "2") (pinfunction "2_2") (pintype "passive"))
    )
    (net (code "90") (name "Net-(JP7-Pad2)") (class "Default")
      (node (ref "JP7") (pin "2") (pinfunction "2_2") (pintype "passive"))
      (node (ref "R31") (pin "2") (pinfunction "2_2") (pintype "passive"))
    )
    (net (code "91") (name "Net-(JP7-Pad3)") (class "Default")
      (node (ref "JP7") (pin "3") (pinfunction "3_3") (pintype "passive"))
      (node (ref "R35") (pin "2") (pinfunction "2_2") (pintype "passive"))
    )
    (net (code "92") (name "Net-(JP8-Pad2)") (class "Default")
      (node (ref "JP8") (pin "2") (pinfunction "2_2") (pintype "passive"))
      (node (ref "R39") (pin "2") (pinfunction "2_2") (pintype "passive"))
    )
    (net (code "93") (name "Net-(JP8-Pad3)") (class "Default")
      (node (ref "JP8") (pin "3") (pinfunction "3_3") (pintype "passive"))
      (node (ref "R42") (pin "2") (pinfunction "2_2") (pintype "passive"))
    )
    (net (code "94") (name "Net-(JP9-Pad2)") (class "Default")
      (node (ref "JP9") (pin "2") (pinfunction "2_2") (pintype "passive"))
      (node (ref "R70") (pin "2") (pinfunction "2_2") (pintype "passive"))
    )
    (net (code "95") (name "Net-(JP9-Pad3)") (class "Default")
      (node (ref "JP9") (pin "3") (pinfunction "3_3") (pintype "passive"))
      (node (ref "R72") (pin "2") (pinfunction "2_2") (pintype "passive"))
    )
    (net (code "96") (name "Net-(JP10-Pad2)") (class "Default")
      (node (ref "JP10") (pin "2") (pinfunction "2_2") (pintype "passive"))
      (node (ref "R74") (pin "2") (pinfunction "2_2") (pintype "passive"))
    )
    (net (code "97") (name "Net-(JP10-Pad3)") (class "Default")
      (node (ref "JP10") (pin "3") (pinfunction "3_3") (pintype "passive"))
      (node (ref "R76") (pin "2") (pinfunction "2_2") (pintype "passive"))
    )
    (net (code "98") (name "Net-(JP11-Pad1)") (class "Default")
      (node (ref "JP11") (pin "1") (pinfunction "1_1") (pintype "passive"))
      (node (ref "JP14") (pin "TIP") (pinfunction "TIP_TIP") (pintype "bidirectional"))
      (node (ref "R112") (pin "1") (pinfunction "1_1") (pintype "passive"))
    )
    (net (code "99") (name "Net-(JP11-Pad2)") (class "Default")
      (node (ref "JP11") (pin "2") (pinfunction "2_2") (pintype "passive"))
      (node (ref "JP14") (pin "RING") (pinfunction "RING_RING") (pintype "bidirectional"))
      (node (ref "R111") (pin "1") (pinfunction "1_1") (pintype "passive"))
    )
    (net (code "100") (name "Net-(JP12-Pad2)") (class "Default")
      (node (ref "JP12") (pin "2") (pinfunction "2_2") (pintype "passive"))
      (node (ref "R78") (pin "2") (pinfunction "2_2") (pintype "passive"))
    )
    (net (code "101") (name "Net-(JP12-Pad3)") (class "Default")
      (node (ref "JP12") (pin "3") (pinfunction "3_3") (pintype "passive"))
      (node (ref "R85") (pin "2") (pinfunction "2_2") (pintype "passive"))
    )
    (net (code "102") (name "Net-(JP13-Pad2)") (class "Default")
      (node (ref "JP13") (pin "2") (pinfunction "2_2") (pintype "passive"))
      (node (ref "R87") (pin "2") (pinfunction "2_2") (pintype "passive"))
    )
    (net (code "103") (name "Net-(JP13-Pad3)") (class "Default")
      (node (ref "JP13") (pin "3") (pinfunction "3_3") (pintype "passive"))
      (node (ref "R88") (pin "2") (pinfunction "2_2") (pintype "passive"))
    )
    (net (code "104") (name "Net-(JP15-Pad2)") (class "Default")
      (node (ref "JP15") (pin "2") (pinfunction "2_2") (pintype "passive"))
      (node (ref "R136") (pin "2") (pinfunction "2_2") (pintype "passive"))
    )
    (net (code "105") (name "Net-(JP15-Pad3)") (class "Default")
      (node (ref "JP15") (pin "3") (pinfunction "3_3") (pintype "passive"))
      (node (ref "R138") (pin "2") (pinfunction "2_2") (pintype "passive"))
    )
    (net (code "106") (name "Net-(JP16-Pad2)") (class "Default")
      (node (ref "JP16") (pin "2") (pinfunction "2_2") (pintype "passive"))
      (node (ref "R140") (pin "2") (pinfunction "2_2") (pintype "passive"))
    )
    (net (code "107") (name "Net-(JP16-Pad3)") (class "Default")
      (node (ref "JP16") (pin "3") (pinfunction "3_3") (pintype "passive"))
      (node (ref "R142") (pin "2") (pinfunction "2_2") (pintype "passive"))
    )
    (net (code "108") (name "Net-(JP17-MIDI_IN)") (class "Default")
      (node (ref "D11") (pin "A") (pinfunction "A_A") (pintype "passive"))
      (node (ref "JP17") (pin "4") (pinfunction "MIDI_IN_4") (pintype "bidirectional"))
      (node (ref "R152") (pin "1") (pinfunction "1_1") (pintype "passive"))
      (node (ref "R159") (pin "2") (pinfunction "2_2") (pintype "passive"))
      (node (ref "U8") (pin "P$3") (pinfunction "C_P$3") (pintype "passive"))
    )
    (net (code "109") (name "Net-(JP17-MIDI_OUT)") (class "Default")
      (node (ref "JP17") (pin "5") (pinfunction "MIDI_OUT_5") (pintype "bidirectional"))
      (node (ref "R156") (pin "1") (pinfunction "1_1") (pintype "passive"))
    )
    (net (code "110") (name "Net-(JP18-Pad2)") (class "Default")
      (node (ref "JP18") (pin "2") (pinfunction "2_2") (pintype "passive"))
      (node (ref "R144") (pin "2") (pinfunction "2_2") (pintype "passive"))
    )
    (net (code "111") (name "Net-(JP18-Pad3)") (class "Default")
      (node (ref "JP18") (pin "3") (pinfunction "3_3") (pintype "passive"))
      (node (ref "R148") (pin "2") (pinfunction "2_2") (pintype "passive"))
    )
    (net (code "112") (name "Net-(JP19-Pad2)") (class "Default")
      (node (ref "JP19") (pin "2") (pinfunction "2_2") (pintype "passive"))
      (node (ref "R150") (pin "2") (pinfunction "2_2") (pintype "passive"))
    )
    (net (code "113") (name "Net-(JP19-Pad3)") (class "Default")
      (node (ref "JP19") (pin "3") (pinfunction "3_3") (pintype "passive"))
      (node (ref "R151") (pin "2") (pinfunction "2_2") (pintype "passive"))
    )
    (net (code "114") (name "Net-(JP20-Pad2)") (class "Default")
      (node (ref "JP20") (pin "2") (pinfunction "2_2") (pintype "passive"))
      (node (ref "R174") (pin "2") (pinfunction "2_2") (pintype "passive"))
    )
    (net (code "115") (name "Net-(JP20-Pad3)") (class "Default")
      (node (ref "JP20") (pin "3") (pinfunction "3_3") (pintype "passive"))
      (node (ref "R176") (pin "2") (pinfunction "2_2") (pintype "passive"))
    )
    (net (code "116") (name "Net-(JP21-Pad2)") (class "Default")
      (node (ref "JP21") (pin "2") (pinfunction "2_2") (pintype "passive"))
      (node (ref "R178") (pin "2") (pinfunction "2_2") (pintype "passive"))
    )
    (net (code "117") (name "Net-(JP21-Pad3)") (class "Default")
      (node (ref "JP21") (pin "3") (pinfunction "3_3") (pintype "passive"))
      (node (ref "R180") (pin "2") (pinfunction "2_2") (pintype "passive"))
    )
    (net (code "118") (name "Net-(JP22-Pad2)") (class "Default")
      (node (ref "JP22") (pin "2") (pinfunction "2_2") (pintype "passive"))
      (node (ref "R182") (pin "2") (pinfunction "2_2") (pintype "passive"))
    )
    (net (code "119") (name "Net-(JP22-Pad3)") (class "Default")
      (node (ref "JP22") (pin "3") (pinfunction "3_3") (pintype "passive"))
      (node (ref "R186") (pin "2") (pinfunction "2_2") (pintype "passive"))
    )
    (net (code "120") (name "Net-(JP23-Pad2)") (class "Default")
      (node (ref "JP23") (pin "2") (pinfunction "2_2") (pintype "passive"))
      (node (ref "R188") (pin "2") (pinfunction "2_2") (pintype "passive"))
    )
    (net (code "121") (name "Net-(JP23-Pad3)") (class "Default")
      (node (ref "JP23") (pin "3") (pinfunction "3_3") (pintype "passive"))
      (node (ref "R189") (pin "2") (pinfunction "2_2") (pintype "passive"))
    )
    (net (code "122") (name "Net-(L1-2)") (class "Default")
      (node (ref "D3") (pin "A") (pinfunction "A_A") (pintype "passive"))
      (node (ref "L1") (pin "P$2") (pinfunction "2_P$2") (pintype "passive"))
      (node (ref "U3") (pin "1") (pinfunction "SW_1") (pintype "bidirectional"))
    )
    (net (code "123") (name "Net-(R1-Pad1)") (class "Default")
      (node (ref "R1") (pin "1") (pinfunction "1_1") (pintype "passive"))
      (node (ref "SW1") (pin "1") (pinfunction "1_1") (pintype "passive"))
    )
    (net (code "124") (name "Net-(R3-Pad1)") (class "Default")
      (node (ref "R3") (pin "1") (pinfunction "1_1") (pintype "passive"))
      (node (ref "SW1") (pin "2") (pinfunction "2_2") (pintype "passive"))
    )
    (net (code "125") (name "Net-(R10-Pad1)") (class "Default")
      (node (ref "R10") (pin "1") (pinfunction "1_1") (pintype "passive"))
      (node (ref "R11") (pin "1") (pinfunction "1_1") (pintype "passive"))
      (node (ref "R12") (pin "1") (pinfunction "1_1") (pintype "passive"))
      (node (ref "R13") (pin "1") (pinfunction "1_1") (pintype "passive"))
      (node (ref "R14") (pin "1") (pinfunction "1_1") (pintype "passive"))
      (node (ref "R15") (pin "1") (pinfunction "1_1") (pintype "passive"))
      (node (ref "R16") (pin "1") (pinfunction "1_1") (pintype "passive"))
      (node (ref "R5") (pin "2") (pinfunction "2_2") (pintype "passive"))
      (node (ref "R6") (pin "2") (pinfunction "2_2") (pintype "passive"))
      (node (ref "R7") (pin "2") (pinfunction "2_2") (pintype "passive"))
      (node (ref "R9") (pin "1") (pinfunction "1_1") (pintype "passive"))
    )
    (net (code "126") (name "Net-(R57-Pad1)") (class "Default")
      (node (ref "R57") (pin "1") (pinfunction "1_1") (pintype "passive"))
      (node (ref "R58") (pin "1") (pinfunction "1_1") (pintype "passive"))
      (node (ref "R59") (pin "1") (pinfunction "1_1") (pintype "passive"))
      (node (ref "R60") (pin "2") (pinfunction "2_2") (pintype "passive"))
      (node (ref "R61") (pin "2") (pinfunction "2_2") (pintype "passive"))
      (node (ref "R62") (pin "2") (pinfunction "2_2") (pintype "passive"))
      (node (ref "R63") (pin "2") (pinfunction "2_2") (pintype "passive"))
      (node (ref "R64") (pin "2") (pinfunction "2_2") (pintype "passive"))
      (node (ref "R65") (pin "2") (pinfunction "2_2") (pintype "passive"))
      (node (ref "R66") (pin "2") (pinfunction "2_2") (pintype "passive"))
      (node (ref "R67") (pin "2") (pinfunction "2_2") (pintype "passive"))
    )
    (net (code "127") (name "Net-(R81-Pad1)") (class "Default")
      (node (ref "R81") (pin "1") (pinfunction "1_1") (pintype "passive"))
      (node (ref "R96") (pin "2") (pinfunction "2_2") (pintype "passive"))
    )
    (net (code "128") (name "Net-(R82-Pad1)") (class "Default")
      (node (ref "R82") (pin "1") (pinfunction "1_1") (pintype "passive"))
      (node (ref "R98") (pin "2") (pinfunction "2_2") (pintype "passive"))
    )
    (net (code "129") (name "Net-(R100-Pad2)") (class "Default")
      (node (ref "R100") (pin "2") (pinfunction "2_2") (pintype "passive"))
      (node (ref "R83") (pin "1") (pinfunction "1_1") (pintype "passive"))
    )
    (net (code "130") (name "Net-(R123-Pad1)") (class "Default")
      (node (ref "R123") (pin "1") (pinfunction "1_1") (pintype "passive"))
      (node (ref "R124") (pin "1") (pinfunction "1_1") (pintype "passive"))
      (node (ref "R125") (pin "1") (pinfunction "1_1") (pintype "passive"))
      (node (ref "R126") (pin "2") (pinfunction "2_2") (pintype "passive"))
      (node (ref "R127") (pin "2") (pinfunction "2_2") (pintype "passive"))
      (node (ref "R128") (pin "2") (pinfunction "2_2") (pintype "passive"))
      (node (ref "R129") (pin "2") (pinfunction "2_2") (pintype "passive"))
      (node (ref "R130") (pin "2") (pinfunction "2_2") (pintype "passive"))
      (node (ref "R131") (pin "2") (pinfunction "2_2") (pintype "passive"))
      (node (ref "R132") (pin "2") (pinfunction "2_2") (pintype "passive"))
      (node (ref "R133") (pin "2") (pinfunction "2_2") (pintype "passive"))
    )
    (net (code "131") (name "Net-(R161-Pad1)") (class "Default")
      (node (ref "R161") (pin "1") (pinfunction "1_1") (pintype "passive"))
      (node (ref "R162") (pin "1") (pinfunction "1_1") (pintype "passive"))
      (node (ref "R163") (pin "1") (pinfunction "1_1") (pintype "passive"))
      (node (ref "R164") (pin "2") (pinfunction "2_2") (pintype "passive"))
      (node (ref "R165") (pin "2") (pinfunction "2_2") (pintype "passive"))
      (node (ref "R166") (pin "2") (pinfunction "2_2") (pintype "passive"))
      (node (ref "R167") (pin "2") (pinfunction "2_2") (pintype "passive"))
      (node (ref "R168") (pin "2") (pinfunction "2_2") (pintype "passive"))
      (node (ref "R169") (pin "2") (pinfunction "2_2") (pintype "passive"))
      (node (ref "R170") (pin "2") (pinfunction "2_2") (pintype "passive"))
      (node (ref "R171") (pin "2") (pinfunction "2_2") (pintype "passive"))
    )
    (net (code "132") (name "Net-(U1-AUX_IN)") (class "Default")
      (node (ref "C25") (pin "2") (pinfunction "2_2") (pintype "passive"))
      (node (ref "U1") (pin "P$9") (pinfunction "AUX_IN_P$9") (pintype "bidirectional"))
    )
    (net (code "133") (name "Net-(U1-IN+)") (class "Default")
      (node (ref "C34") (pin "1") (pinfunction "1_1") (pintype "passive"))
      (node (ref "D1") (pin "A") (pinfunction "A_A") (pintype "passive"))
      (node (ref "D7") (pin "C") (pinfunction "C_C") (pintype "passive"))
      (node (ref "R37") (pin "2") (pinfunction "2_2") (pintype "passive"))
      (node (ref "R55") (pin "2") (pinfunction "2_2") (pintype "passive"))
      (node (ref "U1") (pin "P$6") (pinfunction "IN+_P$6") (pintype "bidirectional"))
    )
    (net (code "134") (name "Net-(U1-IN-)") (class "Default")
      (node (ref "C34") (pin "2") (pinfunction "2_2") (pintype "passive"))
      (node (ref "D2") (pin "A") (pinfunction "A_A") (pintype "passive"))
      (node (ref "D8") (pin "C") (pinfunction "C_C") (pintype "passive"))
      (node (ref "R54") (pin "2") (pinfunction "2_2") (pintype "passive"))
      (node (ref "R56") (pin "2") (pinfunction "2_2") (pintype "passive"))
      (node (ref "U1") (pin "P$7") (pinfunction "IN-_P$7") (pintype "bidirectional"))
    )
    (net (code "135") (name "Net-(U2-A1)") (class "Default")
      (node (ref "R18") (pin "2") (pinfunction "2_2") (pintype "passive"))
      (node (ref "U2") (pin "2") (pinfunction "A1_2") (pintype "bidirectional"))
    )
    (net (code "136") (name "Net-(U2-A2)") (class "Default")
      (node (ref "R19") (pin "2") (pinfunction "2_2") (pintype "passive"))
      (node (ref "U2") (pin "3") (pinfunction "A2_3") (pintype "bidirectional"))
    )
    (net (code "137") (name "Net-(U2-A3)") (class "Default")
      (node (ref "R21") (pin "2") (pinfunction "2_2") (pintype "passive"))
      (node (ref "U2") (pin "4") (pinfunction "A3_4") (pintype "bidirectional"))
    )
    (net (code "138") (name "Net-(U2-A4)") (class "Default")
      (node (ref "R26") (pin "2") (pinfunction "2_2") (pintype "passive"))
      (node (ref "U2") (pin "5") (pinfunction "A4_5") (pintype "bidirectional"))
    )
    (net (code "139") (name "Net-(U2-A5)") (class "Default")
      (node (ref "R28") (pin "2") (pinfunction "2_2") (pintype "passive"))
      (node (ref "U2") (pin "6") (pinfunction "A5_6") (pintype "bidirectional"))
    )
    (net (code "140") (name "Net-(U2-A6)") (class "Default")
      (node (ref "R30") (pin "2") (pinfunction "2_2") (pintype "passive"))
      (node (ref "U2") (pin "7") (pinfunction "A6_7") (pintype "bidirectional"))
    )
    (net (code "141") (name "Net-(U2-A7)") (class "Default")
      (node (ref "R34") (pin "2") (pinfunction "2_2") (pintype "passive"))
      (node (ref "U2") (pin "8") (pinfunction "A7_8") (pintype "bidirectional"))
    )
    (net (code "142") (name "Net-(U2-A8)") (class "Default")
      (node (ref "R38") (pin "2") (pinfunction "2_2") (pintype "passive"))
      (node (ref "U2") (pin "9") (pinfunction "A8_9") (pintype "bidirectional"))
    )
    (net (code "143") (name "Net-(U2-OE1)") (class "Default")
      (node (ref "R33") (pin "1") (pinfunction "1_1") (pintype "passive"))
      (node (ref "R47") (pin "2") (pinfunction "2_2") (pintype "passive"))
      (node (ref "U2") (pin "1") (pinfunction "OE1_1") (pintype "bidirectional"))
    )
    (net (code "144") (name "Net-(U2-OE2)") (class "Default")
      (node (ref "R32") (pin "1") (pinfunction "1_1") (pintype "passive"))
      (node (ref "R46") (pin "2") (pinfunction "2_2") (pintype "passive"))
      (node (ref "U2") (pin "19") (pinfunction "OE2_19") (pintype "bidirectional"))
    )
    (net (code "145") (name "Net-(U2-Y1)") (class "Default")
      (node (ref "R20") (pin "1") (pinfunction "1_1") (pintype "passive"))
      (node (ref "U2") (pin "18") (pinfunction "Y1_18") (pintype "bidirectional"))
    )
    (net (code "146") (name "Net-(U2-Y2)") (class "Default")
      (node (ref "R22") (pin "1") (pinfunction "1_1") (pintype "passive"))
      (node (ref "U2") (pin "17") (pinfunction "Y2_17") (pintype "bidirectional"))
    )
    (net (code "147") (name "Net-(U2-Y3)") (class "Default")
      (node (ref "R27") (pin "1") (pinfunction "1_1") (pintype "passive"))
      (node (ref "U2") (pin "16") (pinfunction "Y3_16") (pintype "bidirectional"))
    )
    (net (code "148") (name "Net-(U2-Y4)") (class "Default")
      (node (ref "R29") (pin "1") (pinfunction "1_1") (pintype "passive"))
      (node (ref "U2") (pin "15") (pinfunction "Y4_15") (pintype "bidirectional"))
    )
    (net (code "149") (name "Net-(U2-Y5)") (class "Default")
      (node (ref "R31") (pin "1") (pinfunction "1_1") (pintype "passive"))
      (node (ref "U2") (pin "14") (pinfunction "Y5_14") (pintype "bidirectional"))
    )
    (net (code "150") (name "Net-(U2-Y6)") (class "Default")
      (node (ref "R35") (pin "1") (pinfunction "1_1") (pintype "passive"))
      (node (ref "U2") (pin "13") (pinfunction "Y6_13") (pintype "bidirectional"))
    )
    (net (code "151") (name "Net-(U2-Y7)") (class "Default")
      (node (ref "R39") (pin "1") (pinfunction "1_1") (pintype "passive"))
      (node (ref "U2") (pin "12") (pinfunction "Y7_12") (pintype "bidirectional"))
    )
    (net (code "152") (name "Net-(U2-Y8)") (class "Default")
      (node (ref "R42") (pin "1") (pinfunction "1_1") (pintype "passive"))
      (node (ref "U2") (pin "11") (pinfunction "Y8_11") (pintype "bidirectional"))
    )
    (net (code "153") (name "Net-(U3-COMP)") (class "Default")
      (node (ref "C35") (pin "1") (pinfunction "1_1") (pintype "passive"))
      (node (ref "U3") (pin "7") (pinfunction "COMP_7") (pintype "bidirectional"))
    )
    (net (code "154") (name "Net-(U3-FB)") (class "Default")
      (node (ref "R41") (pin "1") (pinfunction "1_1") (pintype "passive"))
      (node (ref "R49") (pin "2") (pinfunction "2_2") (pintype "passive"))
      (node (ref "R52") (pin "2") (pinfunction "2_2") (pintype "passive"))
      (node (ref "U3") (pin "6") (pinfunction "FB_6") (pintype "bidirectional"))
    )
    (net (code "155") (name "Net-(U3-RT)") (class "Default")
      (node (ref "R51") (pin "2") (pinfunction "2_2") (pintype "passive"))
      (node (ref "U3") (pin "5") (pinfunction "RT_5") (pintype "bidirectional"))
    )
    (net (code "156") (name "Net-(U3-VCC)") (class "Default")
      (node (ref "C45") (pin "1") (pinfunction "1_1") (pintype "passive"))
      (node (ref "U3") (pin "3") (pinfunction "VCC_3") (pintype "bidirectional"))
    )
    (net (code "157") (name "Net-(U4-A1)") (class "Default")
      (node (ref "R68") (pin "2") (pinfunction "2_2") (pintype "passive"))
      (node (ref "U4") (pin "2") (pinfunction "A1_2") (pintype "bidirectional"))
    )
    (net (code "158") (name "Net-(U4-A2)") (class "Default")
      (node (ref "R69") (pin "2") (pinfunction "2_2") (pintype "passive"))
      (node (ref "U4") (pin "3") (pinfunction "A2_3") (pintype "bidirectional"))
    )
    (net (code "159") (name "Net-(U4-A3)") (class "Default")
      (node (ref "R71") (pin "2") (pinfunction "2_2") (pintype "passive"))
      (node (ref "U4") (pin "4") (pinfunction "A3_4") (pintype "bidirectional"))
    )
    (net (code "160") (name "Net-(U4-A4)") (class "Default")
      (node (ref "R73") (pin "2") (pinfunction "2_2") (pintype "passive"))
      (node (ref "U4") (pin "5") (pinfunction "A4_5") (pintype "bidirectional"))
    )
    (net (code "161") (name "Net-(U4-A5)") (class "Default")
      (node (ref "R75") (pin "2") (pinfunction "2_2") (pintype "passive"))
      (node (ref "U4") (pin "6") (pinfunction "A5_6") (pintype "bidirectional"))
    )
    (net (code "162") (name "Net-(U4-A6)") (class "Default")
      (node (ref "R77") (pin "2") (pinfunction "2_2") (pintype "passive"))
      (node (ref "U4") (pin "7") (pinfunction "A6_7") (pintype "bidirectional"))
    )
    (net (code "163") (name "Net-(U4-A7)") (class "Default")
      (node (ref "R84") (pin "2") (pinfunction "2_2") (pintype "passive"))
      (node (ref "U4") (pin "8") (pinfunction "A7_8") (pintype "bidirectional"))
    )
    (net (code "164") (name "Net-(U4-A8)") (class "Default")
      (node (ref "R86") (pin "2") (pinfunction "2_2") (pintype "passive"))
      (node (ref "U4") (pin "9") (pinfunction "A8_9") (pintype "bidirectional"))
    )
    (net (code "165") (name "Net-(U4-OE1)") (class "Default")
      (node (ref "R80") (pin "1") (pinfunction "1_1") (pintype "passive"))
      (node (ref "R93") (pin "2") (pinfunction "2_2") (pintype "passive"))
      (node (ref "U4") (pin "1") (pinfunction "OE1_1") (pintype "bidirectional"))
    )
    (net (code "166") (name "Net-(U4-OE2)") (class "Default")
      (node (ref "R79") (pin "1") (pinfunction "1_1") (pintype "passive"))
      (node (ref "R92") (pin "2") (pinfunction "2_2") (pintype "passive"))
      (node (ref "U4") (pin "19") (pinfunction "OE2_19") (pintype "bidirectional"))
    )
    (net (code "167") (name "Net-(U4-Y1)") (class "Default")
      (node (ref "R70") (pin "1") (pinfunction "1_1") (pintype "passive"))
      (node (ref "U4") (pin "18") (pinfunction "Y1_18") (pintype "bidirectional"))
    )
    (net (code "168") (name "Net-(U4-Y2)") (class "Default")
      (node (ref "R72") (pin "1") (pinfunction "1_1") (pintype "passive"))
      (node (ref "U4") (pin "17") (pinfunction "Y2_17") (pintype "bidirectional"))
    )
    (net (code "169") (name "Net-(U4-Y3)") (class "Default")
      (node (ref "R74") (pin "1") (pinfunction "1_1") (pintype "passive"))
      (node (ref "U4") (pin "16") (pinfunction "Y3_16") (pintype "bidirectional"))
    )
    (net (code "170") (name "Net-(U4-Y4)") (class "Default")
      (node (ref "R76") (pin "1") (pinfunction "1_1") (pintype "passive"))
      (node (ref "U4") (pin "15") (pinfunction "Y4_15") (pintype "bidirectional"))
    )
    (net (code "171") (name "Net-(U4-Y5)") (class "Default")
      (node (ref "R78") (pin "1") (pinfunction "1_1") (pintype "passive"))
      (node (ref "U4") (pin "14") (pinfunction "Y5_14") (pintype "bidirectional"))
    )
    (net (code "172") (name "Net-(U4-Y6)") (class "Default")
      (node (ref "R85") (pin "1") (pinfunction "1_1") (pintype "passive"))
      (node (ref "U4") (pin "13") (pinfunction "Y6_13") (pintype "bidirectional"))
    )
    (net (code "173") (name "Net-(U4-Y7)") (class "Default")
      (node (ref "R87") (pin "1") (pinfunction "1_1") (pintype "passive"))
      (node (ref "U4") (pin "12") (pinfunction "Y7_12") (pintype "bidirectional"))
    )
    (net (code "174") (name "Net-(U4-Y8)") (class "Default")
      (node (ref "R88") (pin "1") (pinfunction "1_1") (pintype "passive"))
      (node (ref "U4") (pin "11") (pinfunction "Y8_11") (pintype "bidirectional"))
    )
    (net (code "175") (name "Net-(U5-PCMCLK)") (class "Default")
      (node (ref "R89") (pin "1") (pinfunction "1_1") (pintype "passive"))
      (node (ref "U5") (pin "7") (pinfunction "PCMCLK_7") (pintype "bidirectional"))
    )
    (net (code "176") (name "Net-(U5-PCMIN)") (class "Default")
      (node (ref "R91") (pin "1") (pinfunction "1_1") (pintype "passive"))
      (node (ref "U5") (pin "9") (pinfunction "PCMIN_9") (pintype "bidirectional"))
    )
    (net (code "177") (name "Net-(U5-PCMOUT)") (class "Default")
      (node (ref "R101") (pin "1") (pinfunction "1_1") (pintype "passive"))
      (node (ref "U5") (pin "10") (pinfunction "PCMOUT_10") (pintype "bidirectional"))
    )
    (net (code "178") (name "Net-(U5-PCMSYNC)") (class "Default")
      (node (ref "R90") (pin "1") (pinfunction "1_1") (pintype "passive"))
      (node (ref "U5") (pin "8") (pinfunction "PCMSYNC_8") (pintype "bidirectional"))
    )
    (net (code "179") (name "Net-(U5-PIO4)") (class "Default")
      (node (ref "R109") (pin "2") (pinfunction "2_2") (pintype "passive"))
      (node (ref "U5") (pin "22") (pinfunction "PIO4_22") (pintype "bidirectional"))
    )
    (net (code "180") (name "Net-(U5-RESET)") (class "Default")
      (node (ref "JP4") (pin "P$1") (pinfunction "P$1_P$1") (pintype "bidirectional"))
      (node (ref "U5") (pin "5") (pinfunction "RESET_5") (pintype "bidirectional"))
    )
    (net (code "181") (name "Net-(U5-UARTCTS)") (class "Default")
      (node (ref "R107") (pin "1") (pinfunction "1_1") (pintype "passive"))
      (node (ref "U5") (pin "16") (pinfunction "UARTCTS_16") (pintype "bidirectional"))
    )
    (net (code "182") (name "Net-(U5-UARTRTS)") (class "Default")
      (node (ref "R105") (pin "1") (pinfunction "1_1") (pintype "passive"))
      (node (ref "U5") (pin "15") (pinfunction "UARTRTS_15") (pintype "bidirectional"))
    )
    (net (code "183") (name "Net-(U5-UARTRX)") (class "Default")
      (node (ref "R102") (pin "1") (pinfunction "1_1") (pintype "passive"))
      (node (ref "U5") (pin "13") (pinfunction "UARTRX_13") (pintype "bidirectional"))
    )
    (net (code "184") (name "Net-(U5-UARTTX)") (class "Default")
      (node (ref "R103") (pin "1") (pinfunction "1_1") (pintype "passive"))
      (node (ref "U5") (pin "14") (pinfunction "UARTTX_14") (pintype "bidirectional"))
    )
    (net (code "185") (name "Net-(U6-CS)") (class "Default")
      (node (ref "R110") (pin "1") (pinfunction "1_1") (pintype "passive"))
      (node (ref "U6") (pin "1") (pinfunction "CS_1") (pintype "bidirectional"))
    )
    (net (code "186") (name "Net-(U6-DIN)") (class "Default")
      (node (ref "R106") (pin "1") (pinfunction "1_1") (pintype "passive"))
      (node (ref "U6") (pin "14") (pinfunction "DIN_14") (pintype "bidirectional"))
    )
    (net (code "187") (name "Net-(U6-DOUT)") (class "Default")
      (node (ref "R108") (pin "1") (pinfunction "1_1") (pintype "passive"))
      (node (ref "U6") (pin "15") (pinfunction "DOUT_15") (pintype "bidirectional"))
    )
    (net (code "188") (name "Net-(U6-SCLK)") (class "Default")
      (node (ref "R104") (pin "1") (pinfunction "1_1") (pintype "passive"))
      (node (ref "U6") (pin "16") (pinfunction "SCLK_16") (pintype "bidirectional"))
    )
    (net (code "189") (name "Net-(U6-VA)") (class "Default")
      (node (ref "C52") (pin "1") (pinfunction "1_1") (pintype "passive"))
      (node (ref "C53") (pin "1") (pinfunction "1_1") (pintype "passive"))
      (node (ref "L2") (pin "2") (pinfunction "2_2") (pintype "passive"))
      (node (ref "U6") (pin "2") (pinfunction "VA_2") (pintype "bidirectional"))
    )
    (net (code "190") (name "Net-(U7-A1)") (class "Default")
      (node (ref "R134") (pin "2") (pinfunction "2_2") (pintype "passive"))
      (node (ref "U7") (pin "2") (pinfunction "A1_2") (pintype "bidirectional"))
    )
    (net (code "191") (name "Net-(U7-A2)") (class "Default")
      (node (ref "R135") (pin "2") (pinfunction "2_2") (pintype "passive"))
      (node (ref "U7") (pin "3") (pinfunction "A2_3") (pintype "bidirectional"))
    )
    (net (code "192") (name "Net-(U7-A3)") (class "Default")
      (node (ref "R137") (pin "2") (pinfunction "2_2") (pintype "passive"))
      (node (ref "U7") (pin "4") (pinfunction "A3_4") (pintype "bidirectional"))
    )
    (net (code "193") (name "Net-(U7-A4)") (class "Default")
      (node (ref "R139") (pin "2") (pinfunction "2_2") (pintype "passive"))
      (node (ref "U7") (pin "5") (pinfunction "A4_5") (pintype "bidirectional"))
    )
    (net (code "194") (name "Net-(U7-A5)") (class "Default")
      (node (ref "R141") (pin "2") (pinfunction "2_2") (pintype "passive"))
      (node (ref "U7") (pin "6") (pinfunction "A5_6") (pintype "bidirectional"))
    )
    (net (code "195") (name "Net-(U7-A6)") (class "Default")
      (node (ref "R143") (pin "2") (pinfunction "2_2") (pintype "passive"))
      (node (ref "U7") (pin "7") (pinfunction "A6_7") (pintype "bidirectional"))
    )
    (net (code "196") (name "Net-(U7-A7)") (class "Default")
      (node (ref "R147") (pin "2") (pinfunction "2_2") (pintype "passive"))
      (node (ref "U7") (pin "8") (pinfunction "A7_8") (pintype "bidirectional"))
    )
    (net (code "197") (name "Net-(U7-A8)") (class "Default")
      (node (ref "R149") (pin "2") (pinfunction "2_2") (pintype "passive"))
      (node (ref "U7") (pin "9") (pinfunction "A8_9") (pintype "bidirectional"))
    )
    (net (code "198") (name "Net-(U7-OE1)") (class "Default")
      (node (ref "R146") (pin "1") (pinfunction "1_1") (pintype "passive"))
      (node (ref "R155") (pin "2") (pinfunction "2_2") (pintype "passive"))
      (node (ref "U7") (pin "1") (pinfunction "OE1_1") (pintype "bidirectional"))
    )
    (net (code "199") (name "Net-(U7-OE2)") (class "Default")
      (node (ref "R145") (pin "1") (pinfunction "1_1") (pintype "passive"))
      (node (ref "R154") (pin "2") (pinfunction "2_2") (pintype "passive"))
      (node (ref "U7") (pin "19") (pinfunction "OE2_19") (pintype "bidirectional"))
    )
    (net (code "200") (name "Net-(U7-Y1)") (class "Default")
      (node (ref "R136") (pin "1") (pinfunction "1_1") (pintype "passive"))
      (node (ref "U7") (pin "18") (pinfunction "Y1_18") (pintype "bidirectional"))
    )
    (net (code "201") (name "Net-(U7-Y2)") (class "Default")
      (node (ref "R138") (pin "1") (pinfunction "1_1") (pintype "passive"))
      (node (ref "U7") (pin "17") (pinfunction "Y2_17") (pintype "bidirectional"))
    )
    (net (code "202") (name "Net-(U7-Y3)") (class "Default")
      (node (ref "R140") (pin "1") (pinfunction "1_1") (pintype "passive"))
      (node (ref "U7") (pin "16") (pinfunction "Y3_16") (pintype "bidirectional"))
    )
    (net (code "203") (name "Net-(U7-Y4)") (class "Default")
      (node (ref "R142") (pin "1") (pinfunction "1_1") (pintype "passive"))
      (node (ref "U7") (pin "15") (pinfunction "Y4_15") (pintype "bidirectional"))
    )
    (net (code "204") (name "Net-(U7-Y5)") (class "Default")
      (node (ref "R144") (pin "1") (pinfunction "1_1") (pintype "passive"))
      (node (ref "U7") (pin "14") (pinfunction "Y5_14") (pintype "bidirectional"))
    )
    (net (code "205") (name "Net-(U7-Y6)") (class "Default")
      (node (ref "R148") (pin "1") (pinfunction "1_1") (pintype "passive"))
      (node (ref "U7") (pin "13") (pinfunction "Y6_13") (pintype "bidirectional"))
    )
    (net (code "206") (name "Net-(U7-Y7)") (class "Default")
      (node (ref "R150") (pin "1") (pinfunction "1_1") (pintype "passive"))
      (node (ref "U7") (pin "12") (pinfunction "Y7_12") (pintype "bidirectional"))
    )
    (net (code "207") (name "Net-(U7-Y8)") (class "Default")
      (node (ref "R151") (pin "1") (pinfunction "1_1") (pintype "passive"))
      (node (ref "U7") (pin "11") (pinfunction "Y8_11") (pintype "bidirectional"))
    )
    (net (code "208") (name "Net-(U8-A)") (class "Default")
      (node (ref "D11") (pin "C") (pinfunction "C_C") (pintype "passive"))
      (node (ref "R153") (pin "1") (pinfunction "1_1") (pintype "passive"))
      (node (ref "R156") (pin "2") (pinfunction "2_2") (pintype "passive"))
      (node (ref "R160") (pin "2") (pinfunction "2_2") (pintype "passive"))
      (node (ref "U8") (pin "P$2") (pinfunction "A_P$2") (pintype "passive"))
    )
    (net (code "209") (name "Net-(U8-VO)") (class "Default")
      (node (ref "R157") (pin "1") (pinfunction "1_1") (pintype "passive"))
      (node (ref "R158") (pin "1") (pinfunction "1_1") (pintype "passive"))
      (node (ref "U8") (pin "P$6") (pinfunction "VO_P$6") (pintype "passive"))
    )
    (net (code "210") (name "Net-(U10-A1)") (class "Default")
      (node (ref "R172") (pin "2") (pinfunction "2_2") (pintype "passive"))
      (node (ref "U10") (pin "2") (pinfunction "A1_2") (pintype "bidirectional"))
    )
    (net (code "211") (name "Net-(U10-A2)") (class "Default")
      (node (ref "R173") (pin "2") (pinfunction "2_2") (pintype "passive"))
      (node (ref "U10") (pin "3") (pinfunction "A2_3") (pintype "bidirectional"))
    )
    (net (code "212") (name "Net-(U10-A3)") (class "Default")
      (node (ref "R175") (pin "2") (pinfunction "2_2") (pintype "passive"))
      (node (ref "U10") (pin "4") (pinfunction "A3_4") (pintype "bidirectional"))
    )
    (net (code "213") (name "Net-(U10-A4)") (class "Default")
      (node (ref "R177") (pin "2") (pinfunction "2_2") (pintype "passive"))
      (node (ref "U10") (pin "5") (pinfunction "A4_5") (pintype "bidirectional"))
    )
    (net (code "214") (name "Net-(U10-A5)") (class "Default")
      (node (ref "R179") (pin "2") (pinfunction "2_2") (pintype "passive"))
      (node (ref "U10") (pin "6") (pinfunction "A5_6") (pintype "bidirectional"))
    )
    (net (code "215") (name "Net-(U10-A6)") (class "Default")
      (node (ref "R181") (pin "2") (pinfunction "2_2") (pintype "passive"))
      (node (ref "U10") (pin "7") (pinfunction "A6_7") (pintype "bidirectional"))
    )
    (net (code "216") (name "Net-(U10-A7)") (class "Default")
      (node (ref "R185") (pin "2") (pinfunction "2_2") (pintype "passive"))
      (node (ref "U10") (pin "8") (pinfunction "A7_8") (pintype "bidirectional"))
    )
    (net (code "217") (name "Net-(U10-A8)") (class "Default")
      (node (ref "R187") (pin "2") (pinfunction "2_2") (pintype "passive"))
      (node (ref "U10") (pin "9") (pinfunction "A8_9") (pintype "bidirectional"))
    )
    (net (code "218") (name "Net-(U10-OE1)") (class "Default")
      (node (ref "R184") (pin "1") (pinfunction "1_1") (pintype "passive"))
      (node (ref "R191") (pin "2") (pinfunction "2_2") (pintype "passive"))
      (node (ref "U10") (pin "1") (pinfunction "OE1_1") (pintype "bidirectional"))
    )
    (net (code "219") (name "Net-(U10-OE2)") (class "Default")
      (node (ref "R183") (pin "1") (pinfunction "1_1") (pintype "passive"))
      (node (ref "R190") (pin "2") (pinfunction "2_2") (pintype "passive"))
      (node (ref "U10") (pin "19") (pinfunction "OE2_19") (pintype "bidirectional"))
    )
    (net (code "220") (name "Net-(U10-Y1)") (class "Default")
      (node (ref "R174") (pin "1") (pinfunction "1_1") (pintype "passive"))
      (node (ref "U10") (pin "18") (pinfunction "Y1_18") (pintype "bidirectional"))
    )
    (net (code "221") (name "Net-(U10-Y2)") (class "Default")
      (node (ref "R176") (pin "1") (pinfunction "1_1") (pintype "passive"))
      (node (ref "U10") (pin "17") (pinfunction "Y2_17") (pintype "bidirectional"))
    )
    (net (code "222") (name "Net-(U10-Y3)") (class "Default")
      (node (ref "R178") (pin "1") (pinfunction "1_1") (pintype "passive"))
      (node (ref "U10") (pin "16") (pinfunction "Y3_16") (pintype "bidirectional"))
    )
    (net (code "223") (name "Net-(U10-Y4)") (class "Default")
      (node (ref "R180") (pin "1") (pinfunction "1_1") (pintype "passive"))
      (node (ref "U10") (pin "15") (pinfunction "Y4_15") (pintype "bidirectional"))
    )
    (net (code "224") (name "Net-(U10-Y5)") (class "Default")
      (node (ref "R182") (pin "1") (pinfunction "1_1") (pintype "passive"))
      (node (ref "U10") (pin "14") (pinfunction "Y5_14") (pintype "bidirectional"))
    )
    (net (code "225") (name "Net-(U10-Y6)") (class "Default")
      (node (ref "R186") (pin "1") (pinfunction "1_1") (pintype "passive"))
      (node (ref "U10") (pin "13") (pinfunction "Y6_13") (pintype "bidirectional"))
    )
    (net (code "226") (name "Net-(U10-Y7)") (class "Default")
      (node (ref "R188") (pin "1") (pinfunction "1_1") (pintype "passive"))
      (node (ref "U10") (pin "12") (pinfunction "Y7_12") (pintype "bidirectional"))
    )
    (net (code "227") (name "Net-(U10-Y8)") (class "Default")
      (node (ref "R189") (pin "1") (pinfunction "1_1") (pintype "passive"))
      (node (ref "U10") (pin "11") (pinfunction "Y8_11") (pintype "bidirectional"))
    )
    (net (code "228") (name "VCC") (class "Default")
      (node (ref "C1") (pin "+") (pinfunction "+_+") (pintype "passive"))
      (node (ref "C10") (pin "P$1") (pinfunction "1_P$1") (pintype "passive"))
      (node (ref "C11") (pin "P$1") (pinfunction "1_P$1") (pintype "passive"))
      (node (ref "C12") (pin "P$1") (pinfunction "1_P$1") (pintype "passive"))
      (node (ref "C13") (pin "P$1") (pinfunction "1_P$1") (pintype "passive"))
      (node (ref "C14") (pin "P$1") (pinfunction "1_P$1") (pintype "passive"))
      (node (ref "C15") (pin "P$1") (pinfunction "1_P$1") (pintype "passive"))
      (node (ref "C16") (pin "P$1") (pinfunction "1_P$1") (pintype "passive"))
      (node (ref "C17") (pin "P$1") (pinfunction "1_P$1") (pintype "passive"))
      (node (ref "C18") (pin "P$1") (pinfunction "1_P$1") (pintype "passive"))
      (node (ref "C19") (pin "P$1") (pinfunction "1_P$1") (pintype "passive"))
      (node (ref "C2") (pin "+") (pinfunction "+_+") (pintype "passive"))
      (node (ref "C20") (pin "P$1") (pinfunction "1_P$1") (pintype "passive"))
      (node (ref "C21") (pin "P$1") (pinfunction "1_P$1") (pintype "passive"))
      (node (ref "C22") (pin "P$1") (pinfunction "1_P$1") (pintype "passive"))
      (node (ref "C23") (pin "1") (pinfunction "1_1") (pintype "passive"))
      (node (ref "C29") (pin "P$1") (pinfunction "1_P$1") (pintype "passive"))
      (node (ref "C3") (pin "+") (pinfunction "+_+") (pintype "passive"))
      (node (ref "C30") (pin "1") (pinfunction "1_1") (pintype "passive"))
      (node (ref "C31") (pin "P$2") (pinfunction "2_P$2") (pintype "passive"))
      (node (ref "C36") (pin "1") (pinfunction "1_1") (pintype "passive"))
      (node (ref "C37") (pin "P$1") (pinfunction "1_P$1") (pintype "passive"))
      (node (ref "C38") (pin "P$1") (pinfunction "1_P$1") (pintype "passive"))
      (node (ref "C39") (pin "P$1") (pinfunction "1_P$1") (pintype "passive"))
      (node (ref "C4") (pin "+") (pinfunction "+_+") (pintype "passive"))
      (node (ref "C43") (pin "P$2") (pinfunction "2_P$2") (pintype "passive"))
      (node (ref "C47") (pin "P$2") (pinfunction "2_P$2") (pintype "passive"))
      (node (ref "C48") (pin "P$2") (pinfunction "2_P$2") (pintype "passive"))
      (node (ref "C49") (pin "P$1") (pinfunction "1_P$1") (pintype "passive"))
      (node (ref "C5") (pin "P$1") (pinfunction "1_P$1") (pintype "passive"))
      (node (ref "C50") (pin "1") (pinfunction "1_1") (pintype "passive"))
      (node (ref "C51") (pin "P$2") (pinfunction "2_P$2") (pintype "passive"))
      (node (ref "C56") (pin "P$2") (pinfunction "2_P$2") (pintype "passive"))
      (node (ref "C6") (pin "P$1") (pinfunction "1_P$1") (pintype "passive"))
      (node (ref "C61") (pin "P$2") (pinfunction "2_P$2") (pintype "passive"))
      (node (ref "C62") (pin "P$2") (pinfunction "2_P$2") (pintype "passive"))
      (node (ref "C63") (pin "P$1") (pinfunction "1_P$1") (pintype "passive"))
      (node (ref "C64") (pin "1") (pinfunction "1_1") (pintype "passive"))
      (node (ref "C65") (pin "P$2") (pinfunction "2_P$2") (pintype "passive"))
      (node (ref "C66") (pin "P$2") (pinfunction "2_P$2") (pintype "passive"))
      (node (ref "C67") (pin "P$2") (pinfunction "2_P$2") (pintype "passive"))
      (node (ref "C7") (pin "P$1") (pinfunction "1_P$1") (pintype "passive"))
      (node (ref "C70") (pin "P$2") (pinfunction "2_P$2") (pintype "passive"))
      (node (ref "C71") (pin "P$1") (pinfunction "1_P$1") (pintype "passive"))
      (node (ref "C72") (pin "1") (pinfunction "1_1") (pintype "passive"))
      (node (ref "C73") (pin "P$2") (pinfunction "2_P$2") (pintype "passive"))
      (node (ref "C74") (pin "P$2") (pinfunction "2_P$2") (pintype "passive"))
      (node (ref "C75") (pin "P$2") (pinfunction "2_P$2") (pintype "passive"))
      (node (ref "C76") (pin "P$2") (pinfunction "2_P$2") (pintype "passive"))
      (node (ref "C8") (pin "P$1") (pinfunction "1_P$1") (pintype "passive"))
      (node (ref "C9") (pin "P$1") (pinfunction "1_P$1") (pintype "passive"))
      (node (ref "J1") (pin "PWR") (pinfunction "PWR_PWR") (pintype "bidirectional"))
      (node (ref "JP10") (pin "4") (pinfunction "4_4") (pintype "passive"))
      (node (ref "JP12") (pin "4") (pinfunction "4_4") (pintype "passive"))
      (node (ref "JP13") (pin "4") (pinfunction "4_4") (pintype "passive"))
      (node (ref "JP15") (pin "4") (pinfunction "4_4") (pintype "passive"))
      (node (ref "JP16") (pin "4") (pinfunction "4_4") (pintype "passive"))
      (node (ref "JP18") (pin "4") (pinfunction "4_4") (pintype "passive"))
      (node (ref "JP19") (pin "4") (pinfunction "4_4") (pintype "passive"))
      (node (ref "JP20") (pin "4") (pinfunction "4_4") (pintype "passive"))
      (node (ref "JP21") (pin "4") (pinfunction "4_4") (pintype "passive"))
      (node (ref "JP22") (pin "4") (pinfunction "4_4") (pintype "passive"))
      (node (ref "JP23") (pin "4") (pinfunction "4_4") (pintype "passive"))
      (node (ref "JP3") (pin "4") (pinfunction "4_4") (pintype "passive"))
      (node (ref "JP6") (pin "4") (pinfunction "4_4") (pintype "passive"))
      (node (ref "JP7") (pin "4") (pinfunction "4_4") (pintype "passive"))
      (node (ref "JP8") (pin "4") (pinfunction "4_4") (pintype "passive"))
      (node (ref "JP9") (pin "4") (pinfunction "4_4") (pintype "passive"))
      (node (ref "L1") (pin "P$1") (pinfunction "1_P$1") (pintype "passive"))
      (node (ref "R124") (pin "2") (pinfunction "2_2") (pintype "passive"))
      (node (ref "R145") (pin "2") (pinfunction "2_2") (pintype "passive"))
      (node (ref "R146") (pin "2") (pinfunction "2_2") (pintype "passive"))
      (node (ref "R162") (pin "2") (pinfunction "2_2") (pintype "passive"))
      (node (ref "R183") (pin "2") (pinfunction "2_2") (pintype "passive"))
      (node (ref "R184") (pin "2") (pinfunction "2_2") (pintype "passive"))
      (node (ref "R32") (pin "2") (pinfunction "2_2") (pintype "passive"))
      (node (ref "R33") (pin "2") (pinfunction "2_2") (pintype "passive"))
      (node (ref "R40") (pin "2") (pinfunction "2_2") (pintype "passive"))
      (node (ref "R44") (pin "2") (pinfunction "2_2") (pintype "passive"))
      (node (ref "R48") (pin "1") (pinfunction "1_1") (pintype "passive"))
      (node (ref "R5") (pin "1") (pinfunction "1_1") (pintype "passive"))
      (node (ref "R58") (pin "2") (pinfunction "2_2") (pintype "passive"))
      (node (ref "R79") (pin "2") (pinfunction "2_2") (pintype "passive"))
      (node (ref "R80") (pin "2") (pinfunction "2_2") (pintype "passive"))
      (node (ref "R94") (pin "2") (pinfunction "2_2") (pintype "passive"))
      (node (ref "R97") (pin "2") (pinfunction "2_2") (pintype "passive"))
      (node (ref "R99") (pin "2") (pinfunction "2_2") (pintype "passive"))
      (node (ref "U10") (pin "20") (pinfunction "VCC_20") (pintype "bidirectional"))
      (node (ref "U2") (pin "20") (pinfunction "VCC_20") (pintype "bidirectional"))
      (node (ref "U3") (pin "2") (pinfunction "VIN_2") (pintype "bidirectional"))
      (node (ref "U4") (pin "20") (pinfunction "VCC_20") (pintype "bidirectional"))
      (node (ref "U7") (pin "20") (pinfunction "VCC_20") (pintype "bidirectional"))
    )
    (net (code "229") (name "VPP") (class "Default")
      (node (ref "C40") (pin "P$1") (pinfunction "1_P$1") (pintype "passive"))
      (node (ref "C41") (pin "P$1") (pinfunction "1_P$1") (pintype "passive"))
      (node (ref "C42") (pin "1") (pinfunction "1_1") (pintype "passive"))
      (node (ref "D3") (pin "C") (pinfunction "C_C") (pintype "passive"))
      (node (ref "R23") (pin "2") (pinfunction "2_2") (pintype "passive"))
      (node (ref "R24") (pin "2") (pinfunction "2_2") (pintype "passive"))
      (node (ref "R41") (pin "2") (pinfunction "2_2") (pintype "passive"))
      (node (ref "R43") (pin "2") (pinfunction "2_2") (pintype "passive"))
    )
    (net (code "230") (name "unconnected-(J1-PadGND)") (class "Default")
      (node (ref "J1") (pin "GND") (pinfunction "GND_GND") (pintype "bidirectional"))
    )
    (net (code "231") (name "unconnected-(JP1A-2V5-PadW2_2V5)") (class "Default")
      (node (ref "JP1") (pin "W2_2V5") (pinfunction "2V5_W2_2V5") (pintype "passive"))
    )
    (net (code "232") (name "unconnected-(JP1A-2V5-PadW2_2V5_2)") (class "Default")
      (node (ref "JP1") (pin "W2_2V5_2") (pinfunction "2V5_W2_2V5_2") (pintype "passive"))
    )
    (net (code "233") (name "unconnected-(JP1A-2V5-PadW2_2V5_3)") (class "Default")
      (node (ref "JP1") (pin "W2_2V5_3") (pinfunction "2V5_W2_2V5_3") (pintype "passive"))
    )
    (net (code "234") (name "unconnected-(JP1A-2V5-PadW2_2V5_4)") (class "Default")
      (node (ref "JP1") (pin "W2_2V5_4") (pinfunction "2V5_W2_2V5_4") (pintype "passive"))
    )
    (net (code "235") (name "unconnected-(JP1A-3V3-PadW2_3V3_2)") (class "Default")
      (node (ref "JP1") (pin "W2_3V3_2") (pinfunction "3V3_W2_3V3_2") (pintype "passive"))
    )
    (net (code "236") (name "unconnected-(JP1A-3V3-PadW2_3V3_3)") (class "Default")
      (node (ref "JP1") (pin "W2_3V3_3") (pinfunction "3V3_W2_3V3_3") (pintype "passive"))
    )
    (net (code "237") (name "unconnected-(JP1A-3V3-PadW2_3V3_4)") (class "Default")
      (node (ref "JP1") (pin "W2_3V3_4") (pinfunction "3V3_W2_3V3_4") (pintype "passive"))
    )
    (net (code "238") (name "unconnected-(JP1A-5V0-PadW2_5V)") (class "Default")
      (node (ref "JP1") (pin "W2_5V") (pinfunction "5V0_W2_5V") (pintype "passive"))
    )
    (net (code "239") (name "unconnected-(JP1A-5V0-PadW2_5V_2)") (class "Default")
      (node (ref "JP1") (pin "W2_5V_2") (pinfunction "5V0_W2_5V_2") (pintype "passive"))
    )
    (net (code "240") (name "unconnected-(JP1A-5V0-PadW2_5V_3)") (class "Default")
      (node (ref "JP1") (pin "W2_5V_3") (pinfunction "5V0_W2_5V_3") (pintype "passive"))
    )
    (net (code "241") (name "unconnected-(JP1A-5V0-PadW2_5V_4)") (class "Default")
      (node (ref "JP1") (pin "W2_5V_4") (pinfunction "5V0_W2_5V_4") (pintype "passive"))
    )
    (net (code "242") (name "unconnected-(JP1B-2V5-PadW3_2V5)") (class "Default")
      (node (ref "JP1") (pin "W3_2V5") (pinfunction "2V5_W3_2V5") (pintype "passive"))
    )
    (net (code "243") (name "unconnected-(JP1B-2V5-PadW3_2V5_2)") (class "Default")
      (node (ref "JP1") (pin "W3_2V5_2") (pinfunction "2V5_W3_2V5_2") (pintype "passive"))
    )
    (net (code "244") (name "unconnected-(JP1B-5V0-PadW3_5V_2)") (class "Default")
      (node (ref "JP1") (pin "W3_5V_2") (pinfunction "5V0_W3_5V_2") (pintype "passive"))
    )
    (net (code "245") (name "unconnected-(JP5-PadRSH)") (class "Default")
      (node (ref "JP5") (pin "RSH") (pinfunction "RSH_RSH") (pintype "bidirectional"))
    )
    (net (code "246") (name "unconnected-(JP5-PadTSH)") (class "Default")
      (node (ref "JP5") (pin "TSH") (pinfunction "TSH_TSH") (pintype "bidirectional"))
    )
    (net (code "247") (name "unconnected-(JP14-PadRSH)") (class "Default")
      (node (ref "JP14") (pin "RSH") (pinfunction "RSH_RSH") (pintype "bidirectional"))
    )
    (net (code "248") (name "unconnected-(JP14-PadTSH)") (class "Default")
      (node (ref "JP14") (pin "TSH") (pinfunction "TSH_TSH") (pintype "bidirectional"))
    )
    (net (code "249") (name "unconnected-(JP17-NC1-Pad1)") (class "Default")
      (node (ref "JP17") (pin "1") (pinfunction "NC1_1") (pintype "bidirectional"))
    )
    (net (code "250") (name "unconnected-(JP17-NC2-Pad2)") (class "Default")
      (node (ref "JP17") (pin "2") (pinfunction "NC2_2") (pintype "bidirectional"))
    )
    (net (code "251") (name "unconnected-(JP17-NC3-Pad3)") (class "Default")
      (node (ref "JP17") (pin "3") (pinfunction "NC3_3") (pintype "bidirectional"))
    )
    (net (code "252") (name "unconnected-(R4-A-Pad1)") (class "Default")
      (node (ref "R4") (pin "1") (pinfunction "A_1") (pintype "passive"))
    )
    (net (code "253") (name "unconnected-(R48-Pad2)") (class "Default")
      (node (ref "R48") (pin "2") (pinfunction "2_2") (pintype "passive"))
    )
    (net (code "254") (name "unconnected-(U5-AIO1-Pad35)") (class "Default")
      (node (ref "U5") (pin "35") (pinfunction "AIO1_35") (pintype "bidirectional"))
    )
    (net (code "255") (name "unconnected-(U5-AIO2-Pad30)") (class "Default")
      (node (ref "U5") (pin "30") (pinfunction "AIO2_30") (pintype "bidirectional"))
    )
    (net (code "256") (name "unconnected-(U5-NC-Pad26)") (class "Default")
      (node (ref "U5") (pin "26") (pinfunction "NC_26") (pintype "bidirectional"))
    )
    (net (code "257") (name "unconnected-(U5-PIO3-Pad20)") (class "Default")
      (node (ref "U5") (pin "20") (pinfunction "PIO3_20") (pintype "bidirectional"))
    )
    (net (code "258") (name "unconnected-(U5-PIO6-Pad3)") (class "Default")
      (node (ref "U5") (pin "3") (pinfunction "PIO6_3") (pintype "bidirectional"))
    )
    (net (code "259") (name "unconnected-(U5-PIO7-Pad4)") (class "Default")
      (node (ref "U5") (pin "4") (pinfunction "PIO7_4") (pintype "bidirectional"))
    )
    (net (code "260") (name "unconnected-(U5-PIO8-Pad31)") (class "Default")
      (node (ref "U5") (pin "31") (pinfunction "PIO8_31") (pintype "bidirectional"))
    )
    (net (code "261") (name "unconnected-(U5-PIO9-Pad32)") (class "Default")
      (node (ref "U5") (pin "32") (pinfunction "PIO9_32") (pintype "bidirectional"))
    )
    (net (code "262") (name "unconnected-(U5-PIO10-Pad33)") (class "Default")
      (node (ref "U5") (pin "33") (pinfunction "PIO10_33") (pintype "bidirectional"))
    )
    (net (code "263") (name "unconnected-(U5-PIO11-Pad34)") (class "Default")
      (node (ref "U5") (pin "34") (pinfunction "PIO11_34") (pintype "bidirectional"))
    )
    (net (code "264") (name "unconnected-(U5-SPICLK-Pad6)") (class "Default")
      (node (ref "U5") (pin "6") (pinfunction "SPICLK_6") (pintype "bidirectional"))
    )
    (net (code "265") (name "unconnected-(U5-SPICSB-Pad23)") (class "Default")
      (node (ref "U5") (pin "23") (pinfunction "SPICSB_23") (pintype "bidirectional"))
    )
    (net (code "266") (name "unconnected-(U5-SPIMISO-Pad24)") (class "Default")
      (node (ref "U5") (pin "24") (pinfunction "SPIMISO_24") (pintype "bidirectional"))
    )
    (net (code "267") (name "unconnected-(U5-SPIMOSI-Pad2)") (class "Default")
      (node (ref "U5") (pin "2") (pinfunction "SPIMOSI_2") (pintype "bidirectional"))
    )
    (net (code "268") (name "unconnected-(U5-USBD+-Pad17)") (class "Default")
      (node (ref "U5") (pin "17") (pinfunction "USBD+_17") (pintype "bidirectional"))
    )
    (net (code "269") (name "unconnected-(U5-USBD--Pad18)") (class "Default")
      (node (ref "U5") (pin "18") (pinfunction "USBD-_18") (pintype "bidirectional"))
    )
    (net (code "270") (name "unconnected-(U8-VB-PadP$7)") (class "Default")
      (node (ref "U8") (pin "P$7") (pinfunction "VB_P$7") (pintype "passive"))
    )
  )
)
